# narvi-dac.net
KiCad netlist of a schematic drawn in EAGLE
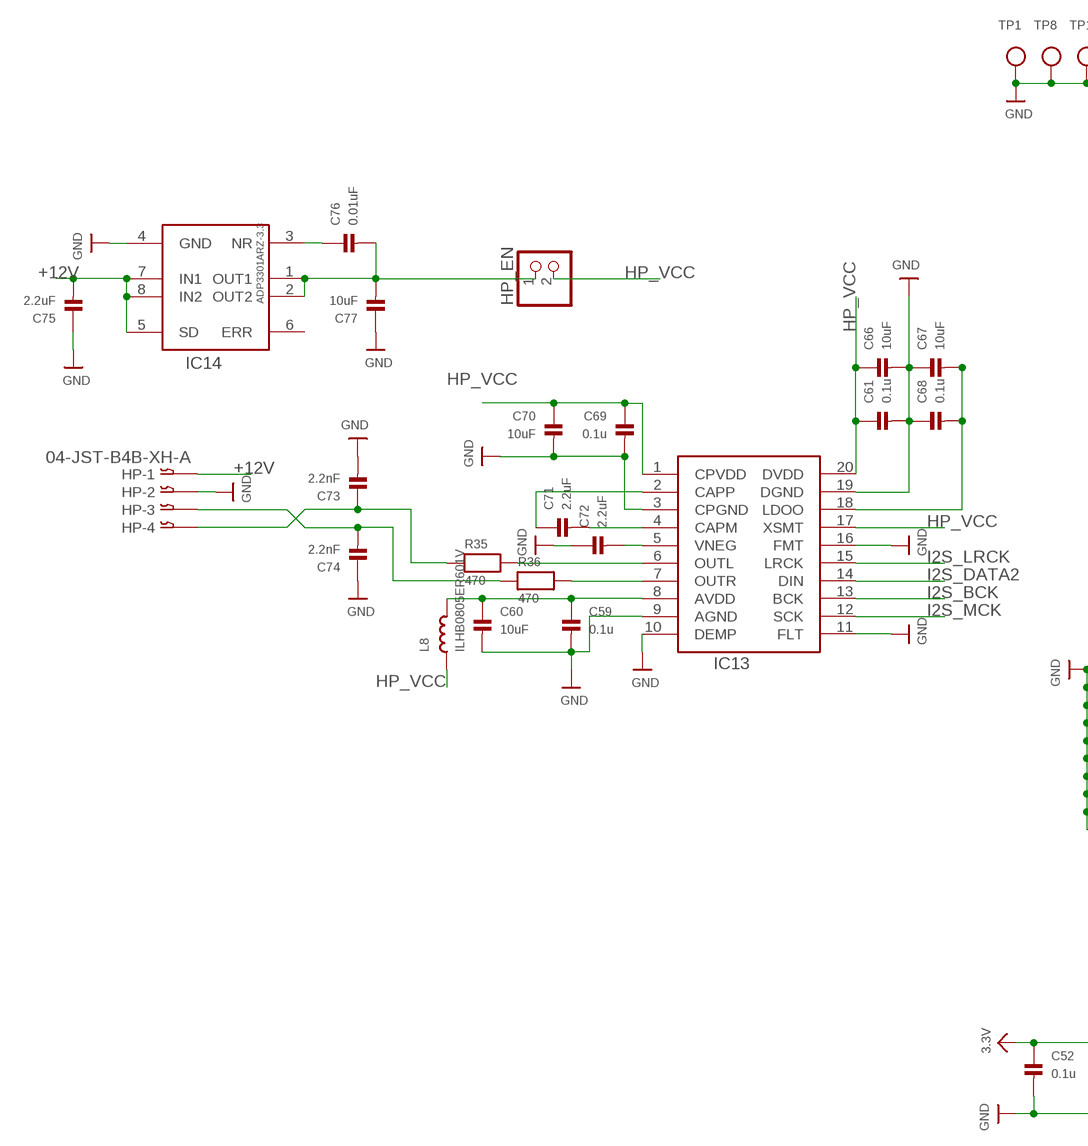
[diagram p0: schematic, sheet 1, part 1 of 2]
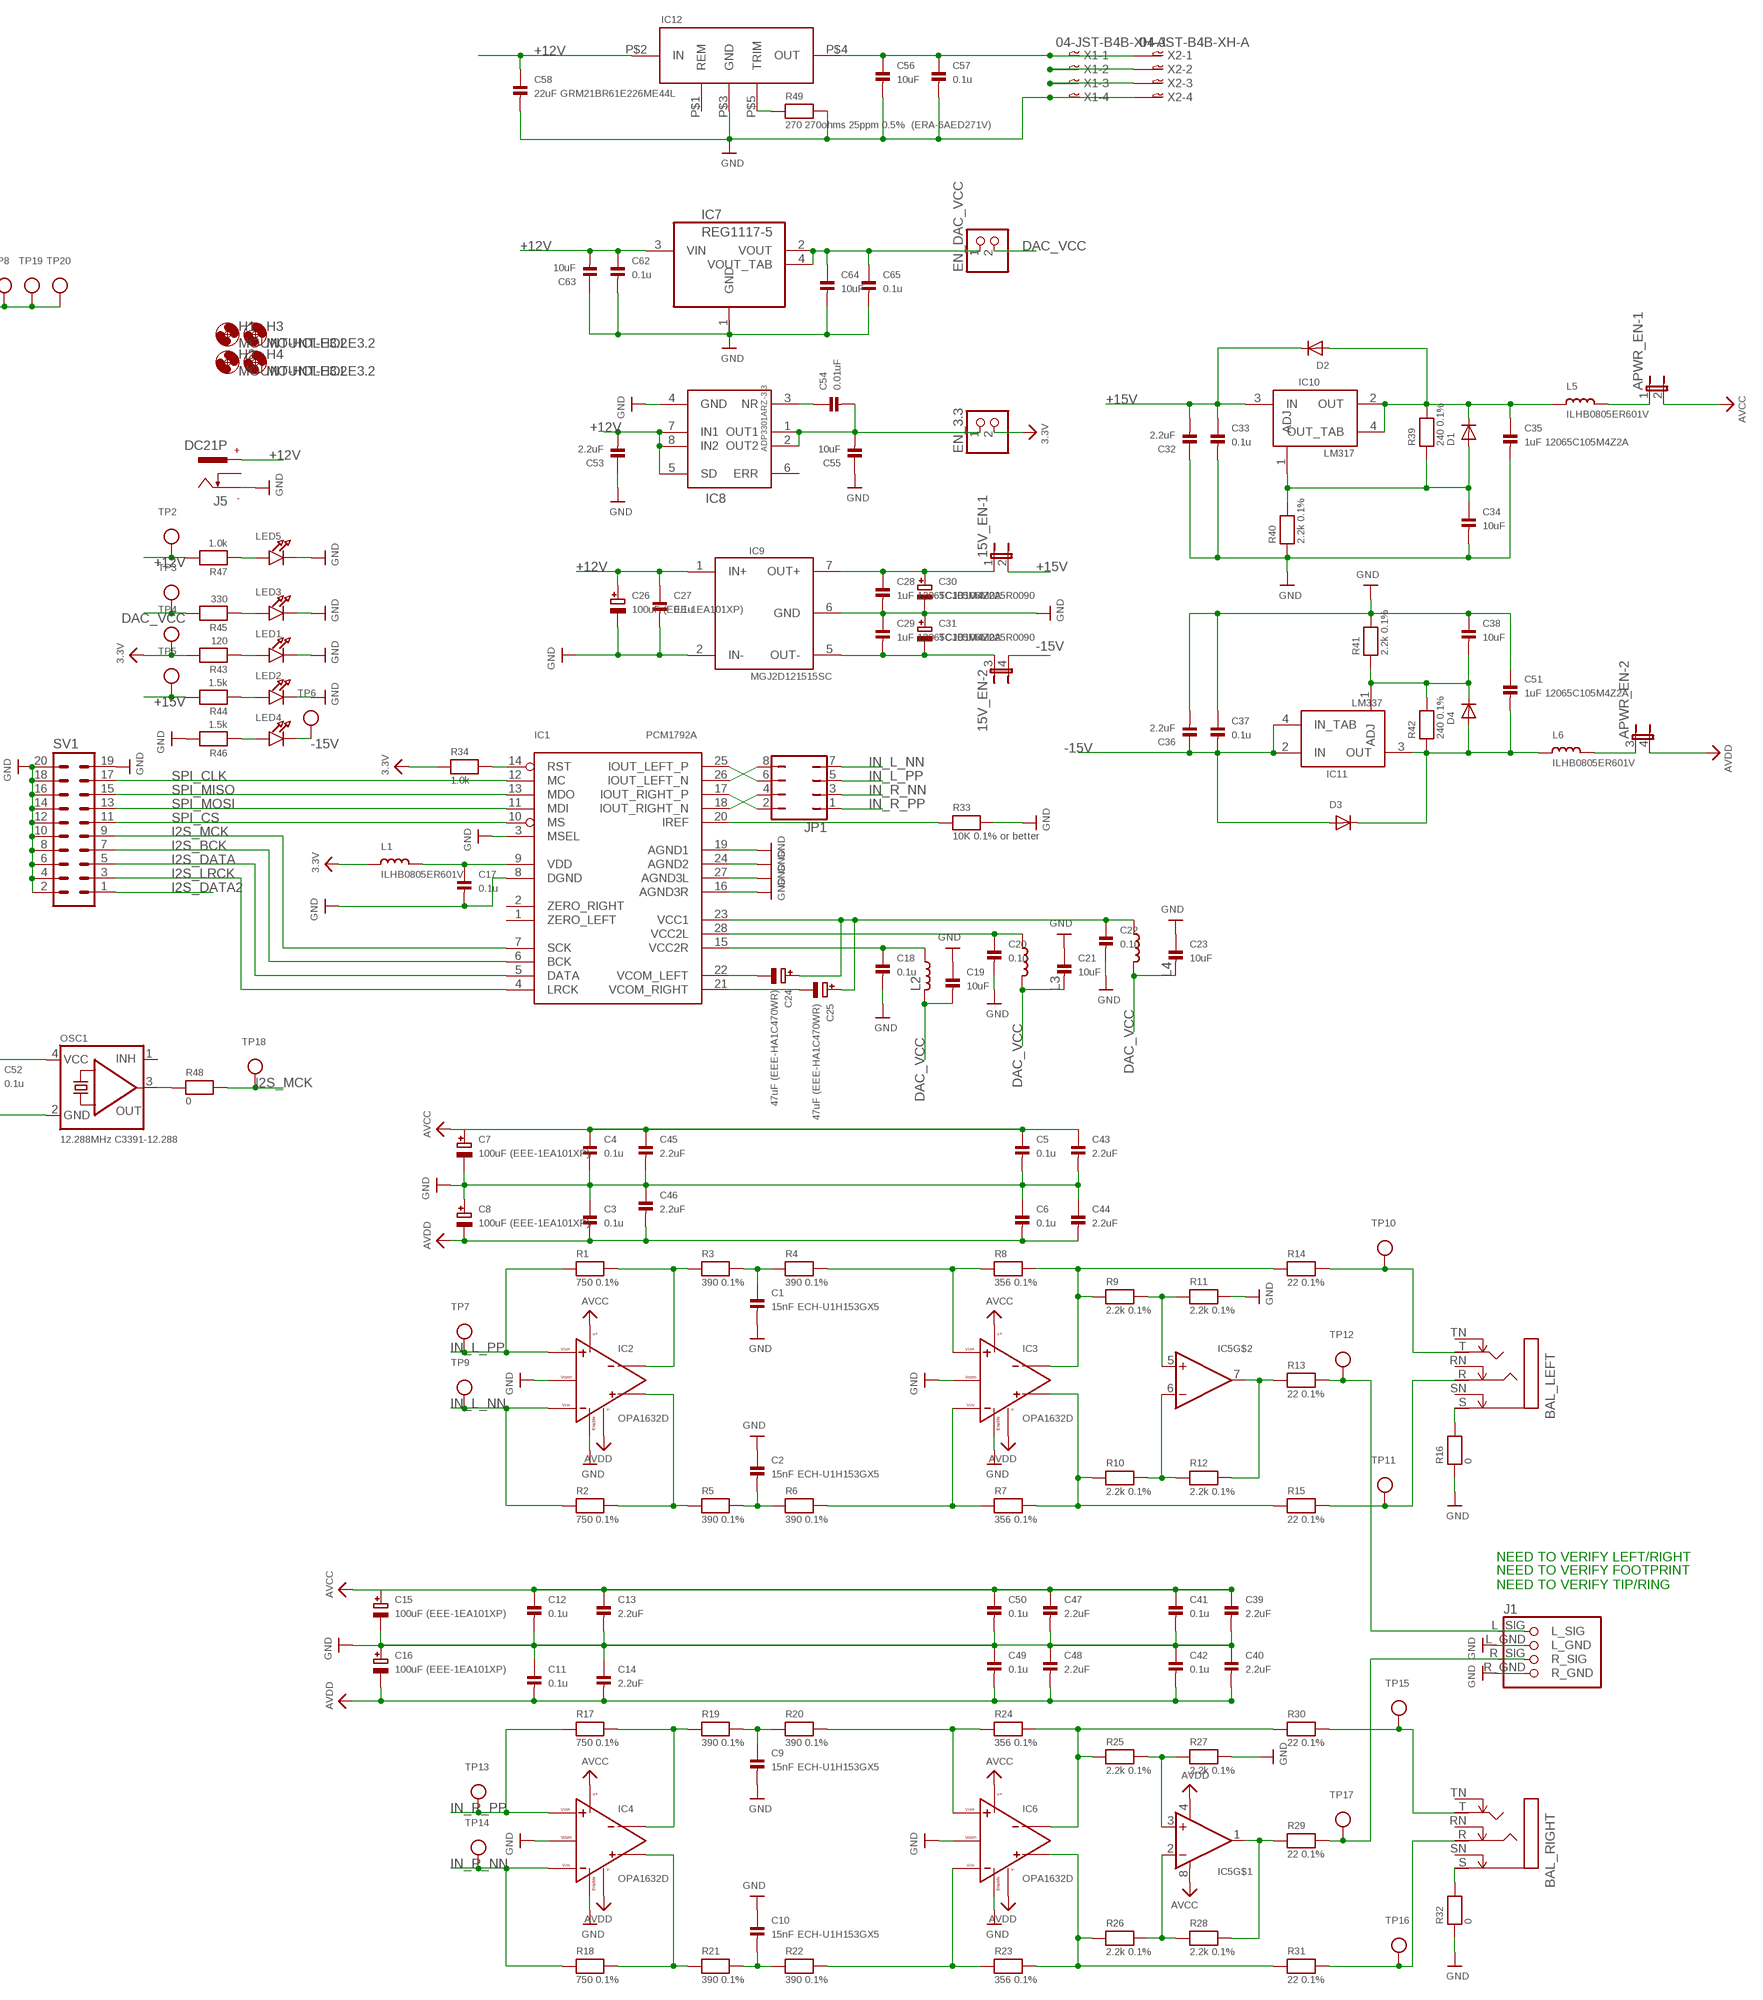
[diagram p1: schematic, sheet 1, part 2 of 2]

(export (version "E")
  (design (tool "Eeschema 10.0.6"))
  (components
    (comp (ref "15V_EN")
      (value "JP2QE")
      (footprint "eagle-import:JP2Q")
      (libsource (lib "eagle-import") (part "JP2QE"))
    )
    (comp (ref "APWR_EN")
      (value "JP2QE")
      (footprint "eagle-import:JP2Q")
      (libsource (lib "eagle-import") (part "JP2QE"))
    )
    (comp (ref "BAL_LEFT")
      (value "STEREOSW")
      (footprint "eagle-import:NMJ6HCD2")
      (libsource (lib "eagle-import") (part "STEREOSW"))
    )
    (comp (ref "BAL_RIGHT")
      (value "STEREOSW")
      (footprint "eagle-import:NMJ6HCD2")
      (libsource (lib "eagle-import") (part "STEREOSW"))
    )
    (comp (ref "C1")
      (value "15nF ECH-U1H153GX5")
      (footprint "eagle-import:1210")
      (libsource (lib "eagle-import") (part "CAP-1210"))
    )
    (comp (ref "C2")
      (value "15nF ECH-U1H153GX5")
      (footprint "eagle-import:1210")
      (libsource (lib "eagle-import") (part "CAP-1210"))
    )
    (comp (ref "C3")
      (value "0.1u")
      (footprint "eagle-import:0603")
      (libsource (lib "eagle-import") (part "CAP_CERAMIC0603"))
    )
    (comp (ref "C4")
      (value "0.1u")
      (footprint "eagle-import:0603")
      (libsource (lib "eagle-import") (part "CAP_CERAMIC0603"))
    )
    (comp (ref "C5")
      (value "0.1u")
      (footprint "eagle-import:0603")
      (libsource (lib "eagle-import") (part "CAP_CERAMIC0603"))
    )
    (comp (ref "C6")
      (value "0.1u")
      (footprint "eagle-import:0603")
      (libsource (lib "eagle-import") (part "CAP_CERAMIC0603"))
    )
    (comp (ref "C7")
      (value "100uF (EEE-1EA101XP)")
      (footprint "eagle-import:PANASONIC_D")
      (libsource (lib "eagle-import") (part "CAP_ELECTROLYTICPANASONIC_D"))
    )
    (comp (ref "C8")
      (value "100uF (EEE-1EA101XP)")
      (footprint "eagle-import:PANASONIC_D")
      (libsource (lib "eagle-import") (part "CAP_ELECTROLYTICPANASONIC_D"))
    )
    (comp (ref "C9")
      (value "15nF ECH-U1H153GX5")
      (footprint "eagle-import:1210")
      (libsource (lib "eagle-import") (part "CAP-1210"))
    )
    (comp (ref "C10")
      (value "15nF ECH-U1H153GX5")
      (footprint "eagle-import:1210")
      (libsource (lib "eagle-import") (part "CAP-1210"))
    )
    (comp (ref "C11")
      (value "0.1u")
      (footprint "eagle-import:0603")
      (libsource (lib "eagle-import") (part "CAP_CERAMIC0603"))
    )
    (comp (ref "C12")
      (value "0.1u")
      (footprint "eagle-import:0603")
      (libsource (lib "eagle-import") (part "CAP_CERAMIC0603"))
    )
    (comp (ref "C13")
      (value "2.2uF")
      (footprint "eagle-import:_0805")
      (libsource (lib "eagle-import") (part "CAP_CERAMIC_0805"))
    )
    (comp (ref "C14")
      (value "2.2uF")
      (footprint "eagle-import:_0805")
      (libsource (lib "eagle-import") (part "CAP_CERAMIC_0805"))
    )
    (comp (ref "C15")
      (value "100uF (EEE-1EA101XP)")
      (footprint "eagle-import:PANASONIC_D")
      (libsource (lib "eagle-import") (part "CAP_ELECTROLYTICPANASONIC_D"))
    )
    (comp (ref "C16")
      (value "100uF (EEE-1EA101XP)")
      (footprint "eagle-import:PANASONIC_D")
      (libsource (lib "eagle-import") (part "CAP_ELECTROLYTICPANASONIC_D"))
    )
    (comp (ref "C17")
      (value "0.1u")
      (footprint "eagle-import:0603")
      (libsource (lib "eagle-import") (part "CAP_CERAMIC0603"))
    )
    (comp (ref "C18")
      (value "0.1u")
      (footprint "eagle-import:0603")
      (libsource (lib "eagle-import") (part "CAP_CERAMIC0603"))
    )
    (comp (ref "C19")
      (value "10uF")
      (footprint "eagle-import:0805")
      (libsource (lib "eagle-import") (part "CAP_CERAMIC0805"))
    )
    (comp (ref "C20")
      (value "0.1u")
      (footprint "eagle-import:0603")
      (libsource (lib "eagle-import") (part "CAP_CERAMIC0603"))
    )
    (comp (ref "C21")
      (value "10uF")
      (footprint "eagle-import:0805")
      (libsource (lib "eagle-import") (part "CAP_CERAMIC0805"))
    )
    (comp (ref "C22")
      (value "0.1u")
      (footprint "eagle-import:0603")
      (libsource (lib "eagle-import") (part "CAP_CERAMIC0603"))
    )
    (comp (ref "C23")
      (value "10uF")
      (footprint "eagle-import:0805")
      (libsource (lib "eagle-import") (part "CAP_CERAMIC0805"))
    )
    (comp (ref "C24")
      (value "47uF (EEE-HA1C470WR)")
      (footprint "eagle-import:PANASONIC_C")
      (libsource (lib "eagle-import") (part "CAP_ELECTROLYTICPANASONIC_C"))
    )
    (comp (ref "C25")
      (value "47uF (EEE-HA1C470WR)")
      (footprint "eagle-import:PANASONIC_C")
      (libsource (lib "eagle-import") (part "CAP_ELECTROLYTICPANASONIC_C"))
    )
    (comp (ref "C26")
      (value "100uF (EEE-1EA101XP)")
      (footprint "eagle-import:PANASONIC_D")
      (libsource (lib "eagle-import") (part "CAP_ELECTROLYTICPANASONIC_D"))
    )
    (comp (ref "C27")
      (value "0.1u")
      (footprint "eagle-import:0603")
      (libsource (lib "eagle-import") (part "CAP_CERAMIC0603"))
    )
    (comp (ref "C28")
      (value "1uF 12065C105M4Z2A")
      (footprint "eagle-import:1206")
      (libsource (lib "eagle-import") (part "CAP_CERAMIC1206"))
    )
    (comp (ref "C29")
      (value "1uF 12065C105M4Z2A")
      (footprint "eagle-import:1206")
      (libsource (lib "eagle-import") (part "CAP_CERAMIC1206"))
    )
    (comp (ref "C30")
      (value "TCJB106M025R0090")
      (footprint "eagle-import:1210POL")
      (libsource (lib "eagle-import") (part "CAP-POL-1210"))
    )
    (comp (ref "C31")
      (value "TCJB106M025R0090")
      (footprint "eagle-import:1210POL")
      (libsource (lib "eagle-import") (part "CAP-POL-1210"))
    )
    (comp (ref "C32")
      (value "2.2uF")
      (footprint "eagle-import:_0805")
      (libsource (lib "eagle-import") (part "CAP_CERAMIC_0805"))
    )
    (comp (ref "C33")
      (value "0.1u")
      (footprint "eagle-import:0603")
      (libsource (lib "eagle-import") (part "CAP_CERAMIC0603"))
    )
    (comp (ref "C34")
      (value "10uF")
      (footprint "eagle-import:0805")
      (libsource (lib "eagle-import") (part "CAP_CERAMIC0805"))
    )
    (comp (ref "C35")
      (value "1uF 12065C105M4Z2A")
      (footprint "eagle-import:1206")
      (libsource (lib "eagle-import") (part "CAP_CERAMIC1206"))
    )
    (comp (ref "C36")
      (value "2.2uF")
      (footprint "eagle-import:_0805")
      (libsource (lib "eagle-import") (part "CAP_CERAMIC_0805"))
    )
    (comp (ref "C37")
      (value "0.1u")
      (footprint "eagle-import:0603")
      (libsource (lib "eagle-import") (part "CAP_CERAMIC0603"))
    )
    (comp (ref "C38")
      (value "10uF")
      (footprint "eagle-import:0805")
      (libsource (lib "eagle-import") (part "CAP_CERAMIC0805"))
    )
    (comp (ref "C39")
      (value "2.2uF")
      (footprint "eagle-import:_0805")
      (libsource (lib "eagle-import") (part "CAP_CERAMIC_0805"))
    )
    (comp (ref "C40")
      (value "2.2uF")
      (footprint "eagle-import:_0805")
      (libsource (lib "eagle-import") (part "CAP_CERAMIC_0805"))
    )
    (comp (ref "C41")
      (value "0.1u")
      (footprint "eagle-import:0603")
      (libsource (lib "eagle-import") (part "CAP_CERAMIC0603"))
    )
    (comp (ref "C42")
      (value "0.1u")
      (footprint "eagle-import:0603")
      (libsource (lib "eagle-import") (part "CAP_CERAMIC0603"))
    )
    (comp (ref "C43")
      (value "2.2uF")
      (footprint "eagle-import:_0805")
      (libsource (lib "eagle-import") (part "CAP_CERAMIC_0805"))
    )
    (comp (ref "C44")
      (value "2.2uF")
      (footprint "eagle-import:_0805")
      (libsource (lib "eagle-import") (part "CAP_CERAMIC_0805"))
    )
    (comp (ref "C45")
      (value "2.2uF")
      (footprint "eagle-import:_0805")
      (libsource (lib "eagle-import") (part "CAP_CERAMIC_0805"))
    )
    (comp (ref "C46")
      (value "2.2uF")
      (footprint "eagle-import:_0805")
      (libsource (lib "eagle-import") (part "CAP_CERAMIC_0805"))
    )
    (comp (ref "C47")
      (value "2.2uF")
      (footprint "eagle-import:_0805")
      (libsource (lib "eagle-import") (part "CAP_CERAMIC_0805"))
    )
    (comp (ref "C48")
      (value "2.2uF")
      (footprint "eagle-import:_0805")
      (libsource (lib "eagle-import") (part "CAP_CERAMIC_0805"))
    )
    (comp (ref "C49")
      (value "0.1u")
      (footprint "eagle-import:0603")
      (libsource (lib "eagle-import") (part "CAP_CERAMIC0603"))
    )
    (comp (ref "C50")
      (value "0.1u")
      (footprint "eagle-import:0603")
      (libsource (lib "eagle-import") (part "CAP_CERAMIC0603"))
    )
    (comp (ref "C51")
      (value "1uF 12065C105M4Z2A")
      (footprint "eagle-import:1206")
      (libsource (lib "eagle-import") (part "CAP_CERAMIC1206"))
    )
    (comp (ref "C52")
      (value "0.1u")
      (footprint "eagle-import:0603")
      (libsource (lib "eagle-import") (part "CAP_CERAMIC0603"))
    )
    (comp (ref "C53")
      (value "2.2uF")
      (footprint "eagle-import:_0805")
      (libsource (lib "eagle-import") (part "CAP_CERAMIC_0805"))
    )
    (comp (ref "C54")
      (value "0.01uF")
      (footprint "eagle-import:0603")
      (libsource (lib "eagle-import") (part "CAP_CERAMIC0603"))
    )
    (comp (ref "C55")
      (value "10uF")
      (footprint "eagle-import:0805")
      (libsource (lib "eagle-import") (part "CAP_CERAMIC0805"))
    )
    (comp (ref "C56")
      (value "10uF")
      (footprint "eagle-import:0805")
      (libsource (lib "eagle-import") (part "CAP_CERAMIC0805"))
    )
    (comp (ref "C57")
      (value "0.1u")
      (footprint "eagle-import:0603")
      (libsource (lib "eagle-import") (part "CAP_CERAMIC0603"))
    )
    (comp (ref "C58")
      (value "22uF GRM21BR61E226ME44L")
      (footprint "eagle-import:_0805")
      (libsource (lib "eagle-import") (part "CAP_CERAMIC_0805"))
    )
    (comp (ref "C59")
      (value "0.1u")
      (footprint "eagle-import:0603")
      (libsource (lib "eagle-import") (part "CAP_CERAMIC0603"))
    )
    (comp (ref "C60")
      (value "10uF")
      (footprint "eagle-import:0805")
      (libsource (lib "eagle-import") (part "CAP_CERAMIC0805"))
    )
    (comp (ref "C61")
      (value "0.1u")
      (footprint "eagle-import:0603")
      (libsource (lib "eagle-import") (part "CAP_CERAMIC0603"))
    )
    (comp (ref "C62")
      (value "0.1u")
      (footprint "eagle-import:0603")
      (libsource (lib "eagle-import") (part "CAP_CERAMIC0603"))
    )
    (comp (ref "C63")
      (value "10uF")
      (footprint "eagle-import:0805")
      (libsource (lib "eagle-import") (part "CAP_CERAMIC0805"))
    )
    (comp (ref "C64")
      (value "10uF")
      (footprint "eagle-import:0805")
      (libsource (lib "eagle-import") (part "CAP_CERAMIC0805"))
    )
    (comp (ref "C65")
      (value "0.1u")
      (footprint "eagle-import:0603")
      (libsource (lib "eagle-import") (part "CAP_CERAMIC0603"))
    )
    (comp (ref "C66")
      (value "10uF")
      (footprint "eagle-import:0805")
      (libsource (lib "eagle-import") (part "CAP_CERAMIC0805"))
    )
    (comp (ref "C67")
      (value "10uF")
      (footprint "eagle-import:0805")
      (libsource (lib "eagle-import") (part "CAP_CERAMIC0805"))
    )
    (comp (ref "C68")
      (value "0.1u")
      (footprint "eagle-import:0603")
      (libsource (lib "eagle-import") (part "CAP_CERAMIC0603"))
    )
    (comp (ref "C69")
      (value "0.1u")
      (footprint "eagle-import:0603")
      (libsource (lib "eagle-import") (part "CAP_CERAMIC0603"))
    )
    (comp (ref "C70")
      (value "10uF")
      (footprint "eagle-import:0805")
      (libsource (lib "eagle-import") (part "CAP_CERAMIC0805"))
    )
    (comp (ref "C71")
      (value "2.2uF")
      (footprint "eagle-import:_0805")
      (libsource (lib "eagle-import") (part "CAP_CERAMIC_0805"))
    )
    (comp (ref "C72")
      (value "2.2uF")
      (footprint "eagle-import:_0805")
      (libsource (lib "eagle-import") (part "CAP_CERAMIC_0805"))
    )
    (comp (ref "C73")
      (value "2.2nF")
      (footprint "eagle-import:_0805")
      (libsource (lib "eagle-import") (part "CAP_CERAMIC_0805"))
    )
    (comp (ref "C74")
      (value "2.2nF")
      (footprint "eagle-import:_0805")
      (libsource (lib "eagle-import") (part "CAP_CERAMIC_0805"))
    )
    (comp (ref "C75")
      (value "2.2uF")
      (footprint "eagle-import:_0805")
      (libsource (lib "eagle-import") (part "CAP_CERAMIC_0805"))
    )
    (comp (ref "C76")
      (value "0.01uF")
      (footprint "eagle-import:0603")
      (libsource (lib "eagle-import") (part "CAP_CERAMIC0603"))
    )
    (comp (ref "C77")
      (value "10uF")
      (footprint "eagle-import:0805")
      (libsource (lib "eagle-import") (part "CAP_CERAMIC0805"))
    )
    (comp (ref "D1")
      (value "DIODESOD-123")
      (footprint "eagle-import:SOD-123")
      (libsource (lib "eagle-import") (part "DIODESOD-123"))
    )
    (comp (ref "D2")
      (value "DIODESOD-123")
      (footprint "eagle-import:SOD-123")
      (libsource (lib "eagle-import") (part "DIODESOD-123"))
    )
    (comp (ref "D3")
      (value "DIODESOD-123")
      (footprint "eagle-import:SOD-123")
      (libsource (lib "eagle-import") (part "DIODESOD-123"))
    )
    (comp (ref "D4")
      (value "DIODESOD-123")
      (footprint "eagle-import:SOD-123")
      (libsource (lib "eagle-import") (part "DIODESOD-123"))
    )
    (comp (ref "EN_3.3")
      (value "HEADER-1X2")
      (footprint "eagle-import:1X02_OVAL")
      (libsource (lib "eagle-import") (part "HEADER-1X2"))
    )
    (comp (ref "EN_DAC_VCC")
      (value "HEADER-1X2")
      (footprint "eagle-import:1X02_OVAL")
      (libsource (lib "eagle-import") (part "HEADER-1X2"))
    )
    (comp (ref "H1")
      (value "MOUNT-HOLE3.2")
      (footprint "eagle-import:3,2")
      (libsource (lib "eagle-import") (part "MOUNT-HOLE3.2"))
    )
    (comp (ref "H2")
      (value "MOUNT-HOLE3.2")
      (footprint "eagle-import:3,2")
      (libsource (lib "eagle-import") (part "MOUNT-HOLE3.2"))
    )
    (comp (ref "H3")
      (value "MOUNT-HOLE3.2")
      (footprint "eagle-import:3,2")
      (libsource (lib "eagle-import") (part "MOUNT-HOLE3.2"))
    )
    (comp (ref "H4")
      (value "MOUNT-HOLE3.2")
      (footprint "eagle-import:3,2")
      (libsource (lib "eagle-import") (part "MOUNT-HOLE3.2"))
    )
    (comp (ref "HP")
      (value "04-JST-B4B-XH-A")
      (footprint "eagle-import:B4B-XH")
      (fields (field (name "MPN") "B4B-XH-A(LF)(SN)"))
      (libsource (lib "eagle-import") (part "04-JST-B4B-XH-A"))
    )
    (comp (ref "HP_EN")
      (value "HEADER-1X2")
      (footprint "eagle-import:1X02_OVAL")
      (libsource (lib "eagle-import") (part "HEADER-1X2"))
    )
    (comp (ref "IC1")
      (value "PCM1792A")
      (footprint "eagle-import:SSOP28")
      (libsource (lib "eagle-import") (part "PCM1792A"))
    )
    (comp (ref "IC2")
      (value "OPA1632D")
      (footprint "eagle-import:SO08")
      (libsource (lib "eagle-import") (part "OPA1632D"))
    )
    (comp (ref "IC3")
      (value "OPA1632D")
      (footprint "eagle-import:SO08")
      (libsource (lib "eagle-import") (part "OPA1632D"))
    )
    (comp (ref "IC4")
      (value "OPA1632D")
      (footprint "eagle-import:SO08")
      (libsource (lib "eagle-import") (part "OPA1632D"))
    )
    (comp (ref "IC5")
      (value "LM4562")
      (footprint "eagle-import:SOIC8_150MIL")
      (libsource (lib "eagle-import") (part "LM4562"))
    )
    (comp (ref "IC6")
      (value "OPA1632D")
      (footprint "eagle-import:SO08")
      (libsource (lib "eagle-import") (part "OPA1632D"))
    )
    (comp (ref "IC7")
      (value "REG1117-5")
      (footprint "eagle-import:SOT223")
      (fields (field (name "MPN") "REG1117"))
      (libsource (lib "eagle-import") (part "REG1117"))
    )
    (comp (ref "IC8")
      (value "ADP3301ARZ-3.3")
      (footprint "eagle-import:SO08")
      (libsource (lib "eagle-import") (part "ADP3301"))
    )
    (comp (ref "IC9")
      (value "MGJ2D121515SC")
      (footprint "eagle-import:MURATA-MGJ2")
      (libsource (lib "eagle-import") (part "MURATA-MGJ2"))
    )
    (comp (ref "IC10")
      (value "LM317")
      (footprint "eagle-import:SOT223")
      (libsource (lib "eagle-import") (part "LM317"))
    )
    (comp (ref "IC11")
      (value "LM337")
      (footprint "eagle-import:SOT223")
      (libsource (lib "eagle-import") (part "LM337"))
    )
    (comp (ref "IC12")
      (value "MURATA_OKR-T/10-W12-C")
      (footprint "eagle-import:MURATA_OKR-T_10-W12-C")
      (libsource (lib "eagle-import") (part "MURATA_OKR-T/10-W12-C"))
    )
    (comp (ref "IC13")
      (value "PCM5102")
      (footprint "eagle-import:TSSOP20")
      (libsource (lib "eagle-import") (part "PCM5102"))
    )
    (comp (ref "IC14")
      (value "ADP3301ARZ-3.3")
      (footprint "eagle-import:SO08")
      (libsource (lib "eagle-import") (part "ADP3301"))
    )
    (comp (ref "J1")
      (value "CUI-RCJ-2123")
      (footprint "eagle-import:CUI-RCJ-2123")
      (libsource (lib "eagle-import") (part "CUI-RCJ-2123"))
    )
    (comp (ref "J5")
      (value "DC21P")
      (footprint "eagle-import:CUI-PJ-102AH")
      (libsource (lib "eagle-import") (part "DC21P"))
    )
    (comp (ref "JP1")
      (value "JP4Q")
      (footprint "eagle-import:JP4Q")
      (libsource (lib "eagle-import") (part "JP4Q"))
    )
    (comp (ref "L1")
      (value "ILHB0805ER601V")
      (footprint "eagle-import:_0805")
      (libsource (lib "eagle-import") (part "INDUCTOR_0805"))
    )
    (comp (ref "L2")
      (value "ILHB0805ER601V")
      (footprint "eagle-import:_0805")
      (libsource (lib "eagle-import") (part "INDUCTOR_0805"))
    )
    (comp (ref "L3")
      (value "ILHB0805ER601V")
      (footprint "eagle-import:_0805")
      (libsource (lib "eagle-import") (part "INDUCTOR_0805"))
    )
    (comp (ref "L4")
      (value "ILHB0805ER601V")
      (footprint "eagle-import:_0805")
      (libsource (lib "eagle-import") (part "INDUCTOR_0805"))
    )
    (comp (ref "L5")
      (value "ILHB0805ER601V")
      (footprint "eagle-import:_0805")
      (libsource (lib "eagle-import") (part "INDUCTOR_0805"))
    )
    (comp (ref "L6")
      (value "ILHB0805ER601V")
      (footprint "eagle-import:_0805")
      (libsource (lib "eagle-import") (part "INDUCTOR_0805"))
    )
    (comp (ref "L8")
      (value "ILHB0805ER601V")
      (footprint "eagle-import:_0805")
      (libsource (lib "eagle-import") (part "INDUCTOR_0805"))
    )
    (comp (ref "LED1")
      (value "LED0805")
      (footprint "eagle-import:CHIPLED_0805")
      (libsource (lib "eagle-import") (part "LED0805"))
    )
    (comp (ref "LED2")
      (value "LED0805")
      (footprint "eagle-import:CHIPLED_0805")
      (libsource (lib "eagle-import") (part "LED0805"))
    )
    (comp (ref "LED3")
      (value "LED0805")
      (footprint "eagle-import:CHIPLED_0805")
      (libsource (lib "eagle-import") (part "LED0805"))
    )
    (comp (ref "LED4")
      (value "LED0805")
      (footprint "eagle-import:CHIPLED_0805")
      (libsource (lib "eagle-import") (part "LED0805"))
    )
    (comp (ref "LED5")
      (value "LED0805")
      (footprint "eagle-import:CHIPLED_0805")
      (libsource (lib "eagle-import") (part "LED0805"))
    )
    (comp (ref "OSC1")
      (value "12.288MHz C3391-12.288")
      (footprint "eagle-import:OSC_7X5MM")
      (libsource (lib "eagle-import") (part "OSCILLATOR"))
    )
    (comp (ref "R1")
      (value "750 0.1%")
      (footprint "eagle-import:_0805")
      (libsource (lib "eagle-import") (part "RESISTOR_0805"))
    )
    (comp (ref "R2")
      (value "750 0.1%")
      (footprint "eagle-import:_0805")
      (libsource (lib "eagle-import") (part "RESISTOR_0805"))
    )
    (comp (ref "R3")
      (value "390 0.1%")
      (footprint "eagle-import:_0805")
      (libsource (lib "eagle-import") (part "RESISTOR_0805"))
    )
    (comp (ref "R4")
      (value "390 0.1%")
      (footprint "eagle-import:_0805")
      (libsource (lib "eagle-import") (part "RESISTOR_0805"))
    )
    (comp (ref "R5")
      (value "390 0.1%")
      (footprint "eagle-import:_0805")
      (libsource (lib "eagle-import") (part "RESISTOR_0805"))
    )
    (comp (ref "R6")
      (value "390 0.1%")
      (footprint "eagle-import:_0805")
      (libsource (lib "eagle-import") (part "RESISTOR_0805"))
    )
    (comp (ref "R7")
      (value "356 0.1%")
      (footprint "eagle-import:_0805")
      (libsource (lib "eagle-import") (part "RESISTOR_0805"))
    )
    (comp (ref "R8")
      (value "356 0.1%")
      (footprint "eagle-import:_0805")
      (libsource (lib "eagle-import") (part "RESISTOR_0805"))
    )
    (comp (ref "R9")
      (value "2.2k 0.1%")
      (footprint "eagle-import:_0805")
      (libsource (lib "eagle-import") (part "RESISTOR_0805"))
    )
    (comp (ref "R10")
      (value "2.2k 0.1%")
      (footprint "eagle-import:_0805")
      (libsource (lib "eagle-import") (part "RESISTOR_0805"))
    )
    (comp (ref "R11")
      (value "2.2k 0.1%")
      (footprint "eagle-import:_0805")
      (libsource (lib "eagle-import") (part "RESISTOR_0805"))
    )
    (comp (ref "R12")
      (value "2.2k 0.1%")
      (footprint "eagle-import:_0805")
      (libsource (lib "eagle-import") (part "RESISTOR_0805"))
    )
    (comp (ref "R13")
      (value "22 0.1%")
      (footprint "eagle-import:_0805")
      (libsource (lib "eagle-import") (part "RESISTOR_0805"))
    )
    (comp (ref "R14")
      (value "22 0.1%")
      (footprint "eagle-import:_0805")
      (libsource (lib "eagle-import") (part "RESISTOR_0805"))
    )
    (comp (ref "R15")
      (value "22 0.1%")
      (footprint "eagle-import:_0805")
      (libsource (lib "eagle-import") (part "RESISTOR_0805"))
    )
    (comp (ref "R16")
      (value "0")
      (footprint "eagle-import:_0805")
      (libsource (lib "eagle-import") (part "RESISTOR_0805"))
    )
    (comp (ref "R17")
      (value "750 0.1%")
      (footprint "eagle-import:_0805")
      (libsource (lib "eagle-import") (part "RESISTOR_0805"))
    )
    (comp (ref "R18")
      (value "750 0.1%")
      (footprint "eagle-import:_0805")
      (libsource (lib "eagle-import") (part "RESISTOR_0805"))
    )
    (comp (ref "R19")
      (value "390 0.1%")
      (footprint "eagle-import:_0805")
      (libsource (lib "eagle-import") (part "RESISTOR_0805"))
    )
    (comp (ref "R20")
      (value "390 0.1%")
      (footprint "eagle-import:_0805")
      (libsource (lib "eagle-import") (part "RESISTOR_0805"))
    )
    (comp (ref "R21")
      (value "390 0.1%")
      (footprint "eagle-import:_0805")
      (libsource (lib "eagle-import") (part "RESISTOR_0805"))
    )
    (comp (ref "R22")
      (value "390 0.1%")
      (footprint "eagle-import:_0805")
      (libsource (lib "eagle-import") (part "RESISTOR_0805"))
    )
    (comp (ref "R23")
      (value "356 0.1%")
      (footprint "eagle-import:_0805")
      (libsource (lib "eagle-import") (part "RESISTOR_0805"))
    )
    (comp (ref "R24")
      (value "356 0.1%")
      (footprint "eagle-import:_0805")
      (libsource (lib "eagle-import") (part "RESISTOR_0805"))
    )
    (comp (ref "R25")
      (value "2.2k 0.1%")
      (footprint "eagle-import:_0805")
      (libsource (lib "eagle-import") (part "RESISTOR_0805"))
    )
    (comp (ref "R26")
      (value "2.2k 0.1%")
      (footprint "eagle-import:_0805")
      (libsource (lib "eagle-import") (part "RESISTOR_0805"))
    )
    (comp (ref "R27")
      (value "2.2k 0.1%")
      (footprint "eagle-import:_0805")
      (libsource (lib "eagle-import") (part "RESISTOR_0805"))
    )
    (comp (ref "R28")
      (value "2.2k 0.1%")
      (footprint "eagle-import:_0805")
      (libsource (lib "eagle-import") (part "RESISTOR_0805"))
    )
    (comp (ref "R29")
      (value "22 0.1%")
      (footprint "eagle-import:_0805")
      (libsource (lib "eagle-import") (part "RESISTOR_0805"))
    )
    (comp (ref "R30")
      (value "22 0.1%")
      (footprint "eagle-import:_0805")
      (libsource (lib "eagle-import") (part "RESISTOR_0805"))
    )
    (comp (ref "R31")
      (value "22 0.1%")
      (footprint "eagle-import:_0805")
      (libsource (lib "eagle-import") (part "RESISTOR_0805"))
    )
    (comp (ref "R32")
      (value "0")
      (footprint "eagle-import:_0805")
      (libsource (lib "eagle-import") (part "RESISTOR_0805"))
    )
    (comp (ref "R33")
      (value "10K 0.1% or better")
      (footprint "eagle-import:_0805")
      (libsource (lib "eagle-import") (part "RESISTOR_0805"))
    )
    (comp (ref "R34")
      (value "1.0k")
      (footprint "eagle-import:_0805")
      (libsource (lib "eagle-import") (part "RESISTOR_0805"))
    )
    (comp (ref "R35")
      (value "470")
      (footprint "eagle-import:_0805")
      (libsource (lib "eagle-import") (part "RESISTOR_0805"))
    )
    (comp (ref "R36")
      (value "470")
      (footprint "eagle-import:_0805")
      (libsource (lib "eagle-import") (part "RESISTOR_0805"))
    )
    (comp (ref "R39")
      (value "240 0.1%")
      (footprint "eagle-import:_0805")
      (libsource (lib "eagle-import") (part "RESISTOR_0805"))
    )
    (comp (ref "R40")
      (value "2.2k 0.1%")
      (footprint "eagle-import:_0805")
      (libsource (lib "eagle-import") (part "RESISTOR_0805"))
    )
    (comp (ref "R41")
      (value "2.2k 0.1%")
      (footprint "eagle-import:_0805")
      (libsource (lib "eagle-import") (part "RESISTOR_0805"))
    )
    (comp (ref "R42")
      (value "240 0.1%")
      (footprint "eagle-import:_0805")
      (libsource (lib "eagle-import") (part "RESISTOR_0805"))
    )
    (comp (ref "R43")
      (value "120")
      (footprint "eagle-import:_0805")
      (libsource (lib "eagle-import") (part "RESISTOR_0805"))
    )
    (comp (ref "R44")
      (value "1.5k")
      (footprint "eagle-import:_0805")
      (libsource (lib "eagle-import") (part "RESISTOR_0805"))
    )
    (comp (ref "R45")
      (value "330")
      (footprint "eagle-import:_0805")
      (libsource (lib "eagle-import") (part "RESISTOR_0805"))
    )
    (comp (ref "R46")
      (value "1.5k")
      (footprint "eagle-import:_0805")
      (libsource (lib "eagle-import") (part "RESISTOR_0805"))
    )
    (comp (ref "R47")
      (value "1.0k")
      (footprint "eagle-import:_0805")
      (libsource (lib "eagle-import") (part "RESISTOR_0805"))
    )
    (comp (ref "R48")
      (value "0")
      (footprint "eagle-import:_0805")
      (libsource (lib "eagle-import") (part "RESISTOR_0805"))
    )
    (comp (ref "R49")
      (value "270 270ohms 25ppm 0.5% (ERA-6AED271V)")
      (footprint "eagle-import:_0805")
      (libsource (lib "eagle-import") (part "RESISTOR_0805"))
    )
    (comp (ref "SV1")
      (value "ML20")
      (footprint "eagle-import:ML20")
      (libsource (lib "eagle-import") (part "ML20"))
    )
    (comp (ref "TP1")
      (value "TESTPOINT0.1\"")
      (footprint "eagle-import:1X01_ROUND")
      (libsource (lib "eagle-import") (part "TESTPOINT0.1{dblquote}"))
    )
    (comp (ref "TP2")
      (value "TESTPOINT0.1\"")
      (footprint "eagle-import:1X01_ROUND")
      (libsource (lib "eagle-import") (part "TESTPOINT0.1{dblquote}"))
    )
    (comp (ref "TP3")
      (value "TESTPOINT0.1\"")
      (footprint "eagle-import:1X01_ROUND")
      (libsource (lib "eagle-import") (part "TESTPOINT0.1{dblquote}"))
    )
    (comp (ref "TP4")
      (value "TESTPOINT0.1\"")
      (footprint "eagle-import:1X01_ROUND")
      (libsource (lib "eagle-import") (part "TESTPOINT0.1{dblquote}"))
    )
    (comp (ref "TP5")
      (value "TESTPOINT0.1\"")
      (footprint "eagle-import:1X01_ROUND")
      (libsource (lib "eagle-import") (part "TESTPOINT0.1{dblquote}"))
    )
    (comp (ref "TP6")
      (value "TESTPOINT0.1\"")
      (footprint "eagle-import:1X01_ROUND")
      (libsource (lib "eagle-import") (part "TESTPOINT0.1{dblquote}"))
    )
    (comp (ref "TP7")
      (value "TESTPOINT0.1\"")
      (footprint "eagle-import:1X01_ROUND")
      (libsource (lib "eagle-import") (part "TESTPOINT0.1{dblquote}"))
    )
    (comp (ref "TP8")
      (value "TESTPOINT0.1\"")
      (footprint "eagle-import:1X01_ROUND")
      (libsource (lib "eagle-import") (part "TESTPOINT0.1{dblquote}"))
    )
    (comp (ref "TP9")
      (value "TESTPOINT0.1\"")
      (footprint "eagle-import:1X01_ROUND")
      (libsource (lib "eagle-import") (part "TESTPOINT0.1{dblquote}"))
    )
    (comp (ref "TP10")
      (value "TESTPOINT0.1\"")
      (footprint "eagle-import:1X01_ROUND")
      (libsource (lib "eagle-import") (part "TESTPOINT0.1{dblquote}"))
    )
    (comp (ref "TP11")
      (value "TESTPOINT0.1\"")
      (footprint "eagle-import:1X01_ROUND")
      (libsource (lib "eagle-import") (part "TESTPOINT0.1{dblquote}"))
    )
    (comp (ref "TP12")
      (value "TESTPOINT0.1\"")
      (footprint "eagle-import:1X01_ROUND")
      (libsource (lib "eagle-import") (part "TESTPOINT0.1{dblquote}"))
    )
    (comp (ref "TP13")
      (value "TESTPOINT0.1\"")
      (footprint "eagle-import:1X01_ROUND")
      (libsource (lib "eagle-import") (part "TESTPOINT0.1{dblquote}"))
    )
    (comp (ref "TP14")
      (value "TESTPOINT0.1\"")
      (footprint "eagle-import:1X01_ROUND")
      (libsource (lib "eagle-import") (part "TESTPOINT0.1{dblquote}"))
    )
    (comp (ref "TP15")
      (value "TESTPOINT0.1\"")
      (footprint "eagle-import:1X01_ROUND")
      (libsource (lib "eagle-import") (part "TESTPOINT0.1{dblquote}"))
    )
    (comp (ref "TP16")
      (value "TESTPOINT0.1\"")
      (footprint "eagle-import:1X01_ROUND")
      (libsource (lib "eagle-import") (part "TESTPOINT0.1{dblquote}"))
    )
    (comp (ref "TP17")
      (value "TESTPOINT0.1\"")
      (footprint "eagle-import:1X01_ROUND")
      (libsource (lib "eagle-import") (part "TESTPOINT0.1{dblquote}"))
    )
    (comp (ref "TP18")
      (value "TESTPOINT0.1\"")
      (footprint "eagle-import:1X01_ROUND")
      (libsource (lib "eagle-import") (part "TESTPOINT0.1{dblquote}"))
    )
    (comp (ref "TP19")
      (value "TESTPOINT0.1\"")
      (footprint "eagle-import:1X01_ROUND")
      (libsource (lib "eagle-import") (part "TESTPOINT0.1{dblquote}"))
    )
    (comp (ref "TP20")
      (value "TESTPOINT0.1\"")
      (footprint "eagle-import:1X01_ROUND")
      (libsource (lib "eagle-import") (part "TESTPOINT0.1{dblquote}"))
    )
    (comp (ref "X1")
      (value "04-JST-B4B-XH-A")
      (footprint "eagle-import:B4B-XH")
      (fields (field (name "MPN") "B4B-XH-A(LF)(SN)"))
      (libsource (lib "eagle-import") (part "04-JST-B4B-XH-A"))
    )
    (comp (ref "X2")
      (value "04-JST-B4B-XH-A")
      (footprint "eagle-import:B4B-XH")
      (fields (field (name "MPN") "B4B-XH-A(LF)(SN)"))
      (libsource (lib "eagle-import") (part "04-JST-B4B-XH-A"))
    )
  )
  (nets
    (net (code "1") (name "/+12V") (class "Default")
      (node (ref "C26") (pin "+") (pinfunction "+_+") (pintype "passive"))
      (node (ref "C27") (pin "1") (pinfunction "P$1_1") (pintype "passive"))
      (node (ref "C53") (pin "2") (pinfunction "P$2_2") (pintype "passive"))
      (node (ref "C58") (pin "1") (pinfunction "P$1_1") (pintype "passive"))
      (node (ref "C62") (pin "1") (pinfunction "P$1_1") (pintype "passive"))
      (node (ref "C63") (pin "2") (pinfunction "P$2_2") (pintype "passive"))
      (node (ref "C75") (pin "2") (pinfunction "P$2_2") (pintype "passive"))
      (node (ref "HP") (pin "P$1") (pinfunction "1_P$1") (pintype "passive"))
      (node (ref "IC12") (pin "P$2") (pinfunction "IN_P$2") (pintype "bidirectional"))
      (node (ref "IC14") (pin "5") (pinfunction "SD_5") (pintype "bidirectional"))
      (node (ref "IC14") (pin "7") (pinfunction "IN1_7") (pintype "bidirectional"))
      (node (ref "IC14") (pin "8") (pinfunction "IN2_8") (pintype "bidirectional"))
      (node (ref "IC7") (pin "3") (pinfunction "VIN_3") (pintype "input"))
      (node (ref "IC8") (pin "5") (pinfunction "SD_5") (pintype "bidirectional"))
      (node (ref "IC8") (pin "7") (pinfunction "IN1_7") (pintype "bidirectional"))
      (node (ref "IC8") (pin "8") (pinfunction "IN2_8") (pintype "bidirectional"))
      (node (ref "IC9") (pin "1") (pinfunction "IN+_1") (pintype "bidirectional"))
      (node (ref "J5") (pin "+") (pinfunction "+_+") (pintype "passive"))
      (node (ref "R47") (pin "2") (pinfunction "2_2") (pintype "passive"))
      (node (ref "TP2") (pin "1") (pinfunction "P$1_1") (pintype "bidirectional"))
    )
    (net (code "2") (name "/+15V") (class "Default")
      (node (ref "15V_EN") (pin "2") (pinfunction "2_2") (pintype "passive"))
      (node (ref "C32") (pin "2") (pinfunction "P$2_2") (pintype "passive"))
      (node (ref "C33") (pin "1") (pinfunction "P$1_1") (pintype "passive"))
      (node (ref "D2") (pin "C") (pinfunction "C_C") (pintype "passive"))
      (node (ref "IC10") (pin "3") (pinfunction "IN_3") (pintype "bidirectional"))
      (node (ref "R44") (pin "2") (pinfunction "2_2") (pintype "passive"))
      (node (ref "TP5") (pin "1") (pinfunction "P$1_1") (pintype "bidirectional"))
    )
    (net (code "3") (name "/-15V") (class "Default")
      (node (ref "15V_EN") (pin "4") (pinfunction "2_4") (pintype "passive"))
      (node (ref "C36") (pin "1") (pinfunction "P$1_1") (pintype "passive"))
      (node (ref "C37") (pin "2") (pinfunction "P$2_2") (pintype "passive"))
      (node (ref "D3") (pin "A") (pinfunction "A_A") (pintype "passive"))
      (node (ref "IC11") (pin "2") (pinfunction "IN_2") (pintype "bidirectional"))
      (node (ref "IC11") (pin "4") (pinfunction "IN_TAB_4") (pintype "bidirectional"))
      (node (ref "LED4") (pin "C") (pinfunction "C_C") (pintype "passive"))
      (node (ref "TP6") (pin "1") (pinfunction "P$1_1") (pintype "bidirectional"))
    )
    (net (code "4") (name "/DAC_VCC") (class "Default")
      (node (ref "C19") (pin "2") (pinfunction "P$2_2") (pintype "passive"))
      (node (ref "C21") (pin "2") (pinfunction "P$2_2") (pintype "passive"))
      (node (ref "C23") (pin "2") (pinfunction "P$2_2") (pintype "passive"))
      (node (ref "EN_DAC_VCC") (pin "2") (pinfunction "2_2") (pintype "passive"))
      (node (ref "L2") (pin "2") (pinfunction "2_2") (pintype "passive"))
      (node (ref "L3") (pin "2") (pinfunction "2_2") (pintype "passive"))
      (node (ref "L4") (pin "2") (pinfunction "2_2") (pintype "passive"))
      (node (ref "R45") (pin "2") (pinfunction "2_2") (pintype "passive"))
      (node (ref "TP3") (pin "1") (pinfunction "P$1_1") (pintype "bidirectional"))
    )
    (net (code "5") (name "/HP_VCC") (class "Default")
      (node (ref "C61") (pin "1") (pinfunction "P$1_1") (pintype "passive"))
      (node (ref "C66") (pin "1") (pinfunction "P$1_1") (pintype "passive"))
      (node (ref "C69") (pin "1") (pinfunction "P$1_1") (pintype "passive"))
      (node (ref "C70") (pin "1") (pinfunction "P$1_1") (pintype "passive"))
      (node (ref "HP_EN") (pin "2") (pinfunction "2_2") (pintype "passive"))
      (node (ref "IC13") (pin "1") (pinfunction "CPVDD_1") (pintype "bidirectional"))
      (node (ref "IC13") (pin "17") (pinfunction "XSMT_17") (pintype "bidirectional"))
      (node (ref "IC13") (pin "20") (pinfunction "DVDD_20") (pintype "bidirectional"))
      (node (ref "L8") (pin "1") (pinfunction "1_1") (pintype "passive"))
    )
    (net (code "6") (name "/I2S_BCK") (class "Default")
      (node (ref "IC1") (pin "6") (pinfunction "BCK_6") (pintype "bidirectional"))
      (node (ref "IC13") (pin "13") (pinfunction "BCK_13") (pintype "bidirectional"))
      (node (ref "SV1") (pin "7") (pinfunction "7_7") (pintype "passive"))
    )
    (net (code "7") (name "/I2S_DATA") (class "Default")
      (node (ref "IC1") (pin "5") (pinfunction "DATA_5") (pintype "bidirectional"))
      (node (ref "SV1") (pin "5") (pinfunction "5_5") (pintype "passive"))
    )
    (net (code "8") (name "/I2S_DATA2") (class "Default")
      (node (ref "IC13") (pin "14") (pinfunction "DIN_14") (pintype "bidirectional"))
      (node (ref "SV1") (pin "1") (pinfunction "1_1") (pintype "passive"))
    )
    (net (code "9") (name "/I2S_LRCK") (class "Default")
      (node (ref "IC1") (pin "4") (pinfunction "LRCK_4") (pintype "bidirectional"))
      (node (ref "IC13") (pin "15") (pinfunction "LRCK_15") (pintype "bidirectional"))
      (node (ref "SV1") (pin "3") (pinfunction "3_3") (pintype "passive"))
    )
    (net (code "10") (name "/I2S_MCK") (class "Default")
      (node (ref "IC1") (pin "7") (pinfunction "SCK_7") (pintype "bidirectional"))
      (node (ref "IC13") (pin "12") (pinfunction "SCK_12") (pintype "bidirectional"))
      (node (ref "R48") (pin "2") (pinfunction "2_2") (pintype "passive"))
      (node (ref "SV1") (pin "9") (pinfunction "9_9") (pintype "passive"))
      (node (ref "TP18") (pin "1") (pinfunction "P$1_1") (pintype "bidirectional"))
    )
    (net (code "11") (name "/IN_L_NN") (class "Default")
      (node (ref "IC2") (pin "1") (pinfunction "VIN-_1") (pintype "bidirectional"))
      (node (ref "JP1") (pin "7") (pinfunction "7_7") (pintype "passive"))
      (node (ref "R2") (pin "1") (pinfunction "1_1") (pintype "passive"))
      (node (ref "TP9") (pin "1") (pinfunction "P$1_1") (pintype "bidirectional"))
    )
    (net (code "12") (name "/IN_L_PP") (class "Default")
      (node (ref "IC2") (pin "8") (pinfunction "VIN+_8") (pintype "bidirectional"))
      (node (ref "JP1") (pin "5") (pinfunction "5_5") (pintype "passive"))
      (node (ref "R1") (pin "1") (pinfunction "1_1") (pintype "passive"))
      (node (ref "TP7") (pin "1") (pinfunction "P$1_1") (pintype "bidirectional"))
    )
    (net (code "13") (name "/IN_R_NN") (class "Default")
      (node (ref "IC4") (pin "1") (pinfunction "VIN-_1") (pintype "bidirectional"))
      (node (ref "JP1") (pin "3") (pinfunction "3_3") (pintype "passive"))
      (node (ref "R18") (pin "1") (pinfunction "1_1") (pintype "passive"))
      (node (ref "TP14") (pin "1") (pinfunction "P$1_1") (pintype "bidirectional"))
    )
    (net (code "14") (name "/IN_R_PP") (class "Default")
      (node (ref "IC4") (pin "8") (pinfunction "VIN+_8") (pintype "bidirectional"))
      (node (ref "JP1") (pin "1") (pinfunction "1_1") (pintype "passive"))
      (node (ref "R17") (pin "1") (pinfunction "1_1") (pintype "passive"))
      (node (ref "TP13") (pin "1") (pinfunction "P$1_1") (pintype "bidirectional"))
    )
    (net (code "15") (name "/SPI_CLK") (class "Default")
      (node (ref "IC1") (pin "12") (pinfunction "MC_12") (pintype "bidirectional"))
      (node (ref "SV1") (pin "17") (pinfunction "17_17") (pintype "passive"))
    )
    (net (code "16") (name "/SPI_CS") (class "Default")
      (node (ref "IC1") (pin "10") (pinfunction "MS_10") (pintype "bidirectional"))
      (node (ref "SV1") (pin "11") (pinfunction "11_11") (pintype "passive"))
    )
    (net (code "17") (name "/SPI_MISO") (class "Default")
      (node (ref "IC1") (pin "13") (pinfunction "MDO_13") (pintype "bidirectional"))
      (node (ref "SV1") (pin "15") (pinfunction "15_15") (pintype "passive"))
    )
    (net (code "18") (name "/SPI_MOSI") (class "Default")
      (node (ref "IC1") (pin "11") (pinfunction "MDI_11") (pintype "bidirectional"))
      (node (ref "SV1") (pin "13") (pinfunction "13_13") (pintype "passive"))
    )
    (net (code "19") (name "3.3V") (class "Default")
      (node (ref "C52") (pin "1") (pinfunction "P$1_1") (pintype "passive"))
      (node (ref "EN_3.3") (pin "2") (pinfunction "2_2") (pintype "passive"))
      (node (ref "L1") (pin "1") (pinfunction "1_1") (pintype "passive"))
      (node (ref "OSC1") (pin "4") (pinfunction "VCC_4") (pintype "power_in"))
      (node (ref "R34") (pin "1") (pinfunction "1_1") (pintype "passive"))
      (node (ref "R43") (pin "2") (pinfunction "2_2") (pintype "passive"))
      (node (ref "TP4") (pin "1") (pinfunction "P$1_1") (pintype "bidirectional"))
    )
    (net (code "20") (name "AVCC") (class "Default")
      (node (ref "APWR_EN") (pin "2") (pinfunction "2_2") (pintype "passive"))
      (node (ref "C12") (pin "1") (pinfunction "P$1_1") (pintype "passive"))
      (node (ref "C13") (pin "1") (pinfunction "P$1_1") (pintype "passive"))
      (node (ref "C15") (pin "+") (pinfunction "+_+") (pintype "passive"))
      (node (ref "C39") (pin "1") (pinfunction "P$1_1") (pintype "passive"))
      (node (ref "C4") (pin "1") (pinfunction "P$1_1") (pintype "passive"))
      (node (ref "C41") (pin "1") (pinfunction "P$1_1") (pintype "passive"))
      (node (ref "C43") (pin "1") (pinfunction "P$1_1") (pintype "passive"))
      (node (ref "C45") (pin "1") (pinfunction "P$1_1") (pintype "passive"))
      (node (ref "C47") (pin "1") (pinfunction "P$1_1") (pintype "passive"))
      (node (ref "C5") (pin "1") (pinfunction "P$1_1") (pintype "passive"))
      (node (ref "C50") (pin "1") (pinfunction "P$1_1") (pintype "passive"))
      (node (ref "C7") (pin "+") (pinfunction "+_+") (pintype "passive"))
      (node (ref "IC2") (pin "3") (pinfunction "V+_3") (pintype "bidirectional"))
      (node (ref "IC3") (pin "3") (pinfunction "V+_3") (pintype "bidirectional"))
      (node (ref "IC4") (pin "3") (pinfunction "V+_3") (pintype "bidirectional"))
      (node (ref "IC5") (pin "8") (pinfunction "V+_8") (pintype "power_in"))
      (node (ref "IC6") (pin "3") (pinfunction "V+_3") (pintype "bidirectional"))
    )
    (net (code "21") (name "AVDD") (class "Default")
      (node (ref "APWR_EN") (pin "4") (pinfunction "2_4") (pintype "passive"))
      (node (ref "C11") (pin "2") (pinfunction "P$2_2") (pintype "passive"))
      (node (ref "C14") (pin "2") (pinfunction "P$2_2") (pintype "passive"))
      (node (ref "C16") (pin "-") (pinfunction "-_-") (pintype "passive"))
      (node (ref "C3") (pin "2") (pinfunction "P$2_2") (pintype "passive"))
      (node (ref "C40") (pin "2") (pinfunction "P$2_2") (pintype "passive"))
      (node (ref "C42") (pin "2") (pinfunction "P$2_2") (pintype "passive"))
      (node (ref "C44") (pin "2") (pinfunction "P$2_2") (pintype "passive"))
      (node (ref "C46") (pin "2") (pinfunction "P$2_2") (pintype "passive"))
      (node (ref "C48") (pin "2") (pinfunction "P$2_2") (pintype "passive"))
      (node (ref "C49") (pin "2") (pinfunction "P$2_2") (pintype "passive"))
      (node (ref "C6") (pin "2") (pinfunction "P$2_2") (pintype "passive"))
      (node (ref "C8") (pin "-") (pinfunction "-_-") (pintype "passive"))
      (node (ref "IC2") (pin "6") (pinfunction "V-_6") (pintype "bidirectional"))
      (node (ref "IC3") (pin "6") (pinfunction "V-_6") (pintype "bidirectional"))
      (node (ref "IC4") (pin "6") (pinfunction "V-_6") (pintype "bidirectional"))
      (node (ref "IC5") (pin "4") (pinfunction "V-_4") (pintype "power_in"))
      (node (ref "IC6") (pin "6") (pinfunction "V-_6") (pintype "bidirectional"))
    )
    (net (code "22") (name "GND") (class "Default")
      (node (ref "C1") (pin "2") (pinfunction "P$2_2") (pintype "passive"))
      (node (ref "C10") (pin "1") (pinfunction "P$1_1") (pintype "passive"))
      (node (ref "C11") (pin "1") (pinfunction "P$1_1") (pintype "passive"))
      (node (ref "C12") (pin "2") (pinfunction "P$2_2") (pintype "passive"))
      (node (ref "C13") (pin "2") (pinfunction "P$2_2") (pintype "passive"))
      (node (ref "C14") (pin "1") (pinfunction "P$1_1") (pintype "passive"))
      (node (ref "C15") (pin "-") (pinfunction "-_-") (pintype "passive"))
      (node (ref "C16") (pin "+") (pinfunction "+_+") (pintype "passive"))
      (node (ref "C17") (pin "2") (pinfunction "P$2_2") (pintype "passive"))
      (node (ref "C18") (pin "2") (pinfunction "P$2_2") (pintype "passive"))
      (node (ref "C19") (pin "1") (pinfunction "P$1_1") (pintype "passive"))
      (node (ref "C2") (pin "1") (pinfunction "P$1_1") (pintype "passive"))
      (node (ref "C20") (pin "2") (pinfunction "P$2_2") (pintype "passive"))
      (node (ref "C21") (pin "1") (pinfunction "P$1_1") (pintype "passive"))
      (node (ref "C22") (pin "2") (pinfunction "P$2_2") (pintype "passive"))
      (node (ref "C23") (pin "1") (pinfunction "P$1_1") (pintype "passive"))
      (node (ref "C26") (pin "-") (pinfunction "-_-") (pintype "passive"))
      (node (ref "C27") (pin "2") (pinfunction "P$2_2") (pintype "passive"))
      (node (ref "C28") (pin "2") (pinfunction "P$2_2") (pintype "passive"))
      (node (ref "C29") (pin "1") (pinfunction "P$1_1") (pintype "passive"))
      (node (ref "C3") (pin "1") (pinfunction "P$1_1") (pintype "passive"))
      (node (ref "C30") (pin "2-") (pinfunction "-_2-") (pintype "passive"))
      (node (ref "C31") (pin "1+") (pinfunction "+_1+") (pintype "passive"))
      (node (ref "C32") (pin "1") (pinfunction "P$1_1") (pintype "passive"))
      (node (ref "C33") (pin "2") (pinfunction "P$2_2") (pintype "passive"))
      (node (ref "C34") (pin "2") (pinfunction "P$2_2") (pintype "passive"))
      (node (ref "C35") (pin "2") (pinfunction "P$2_2") (pintype "passive"))
      (node (ref "C36") (pin "2") (pinfunction "P$2_2") (pintype "passive"))
      (node (ref "C37") (pin "1") (pinfunction "P$1_1") (pintype "passive"))
      (node (ref "C38") (pin "1") (pinfunction "P$1_1") (pintype "passive"))
      (node (ref "C39") (pin "2") (pinfunction "P$2_2") (pintype "passive"))
      (node (ref "C4") (pin "2") (pinfunction "P$2_2") (pintype "passive"))
      (node (ref "C40") (pin "1") (pinfunction "P$1_1") (pintype "passive"))
      (node (ref "C41") (pin "2") (pinfunction "P$2_2") (pintype "passive"))
      (node (ref "C42") (pin "1") (pinfunction "P$1_1") (pintype "passive"))
      (node (ref "C43") (pin "2") (pinfunction "P$2_2") (pintype "passive"))
      (node (ref "C44") (pin "1") (pinfunction "P$1_1") (pintype "passive"))
      (node (ref "C45") (pin "2") (pinfunction "P$2_2") (pintype "passive"))
      (node (ref "C46") (pin "1") (pinfunction "P$1_1") (pintype "passive"))
      (node (ref "C47") (pin "2") (pinfunction "P$2_2") (pintype "passive"))
      (node (ref "C48") (pin "1") (pinfunction "P$1_1") (pintype "passive"))
      (node (ref "C49") (pin "1") (pinfunction "P$1_1") (pintype "passive"))
      (node (ref "C5") (pin "2") (pinfunction "P$2_2") (pintype "passive"))
      (node (ref "C50") (pin "2") (pinfunction "P$2_2") (pintype "passive"))
      (node (ref "C51") (pin "1") (pinfunction "P$1_1") (pintype "passive"))
      (node (ref "C52") (pin "2") (pinfunction "P$2_2") (pintype "passive"))
      (node (ref "C53") (pin "1") (pinfunction "P$1_1") (pintype "passive"))
      (node (ref "C55") (pin "1") (pinfunction "P$1_1") (pintype "passive"))
      (node (ref "C56") (pin "2") (pinfunction "P$2_2") (pintype "passive"))
      (node (ref "C57") (pin "2") (pinfunction "P$2_2") (pintype "passive"))
      (node (ref "C58") (pin "2") (pinfunction "P$2_2") (pintype "passive"))
      (node (ref "C59") (pin "2") (pinfunction "P$2_2") (pintype "passive"))
      (node (ref "C6") (pin "1") (pinfunction "P$1_1") (pintype "passive"))
      (node (ref "C60") (pin "2") (pinfunction "P$2_2") (pintype "passive"))
      (node (ref "C61") (pin "2") (pinfunction "P$2_2") (pintype "passive"))
      (node (ref "C62") (pin "2") (pinfunction "P$2_2") (pintype "passive"))
      (node (ref "C63") (pin "1") (pinfunction "P$1_1") (pintype "passive"))
      (node (ref "C64") (pin "2") (pinfunction "P$2_2") (pintype "passive"))
      (node (ref "C65") (pin "2") (pinfunction "P$2_2") (pintype "passive"))
      (node (ref "C66") (pin "2") (pinfunction "P$2_2") (pintype "passive"))
      (node (ref "C67") (pin "1") (pinfunction "P$1_1") (pintype "passive"))
      (node (ref "C68") (pin "1") (pinfunction "P$1_1") (pintype "passive"))
      (node (ref "C69") (pin "2") (pinfunction "P$2_2") (pintype "passive"))
      (node (ref "C7") (pin "-") (pinfunction "-_-") (pintype "passive"))
      (node (ref "C70") (pin "2") (pinfunction "P$2_2") (pintype "passive"))
      (node (ref "C72") (pin "1") (pinfunction "P$1_1") (pintype "passive"))
      (node (ref "C73") (pin "2") (pinfunction "P$2_2") (pintype "passive"))
      (node (ref "C74") (pin "1") (pinfunction "P$1_1") (pintype "passive"))
      (node (ref "C75") (pin "1") (pinfunction "P$1_1") (pintype "passive"))
      (node (ref "C77") (pin "1") (pinfunction "P$1_1") (pintype "passive"))
      (node (ref "C8") (pin "+") (pinfunction "+_+") (pintype "passive"))
      (node (ref "C9") (pin "2") (pinfunction "P$2_2") (pintype "passive"))
      (node (ref "HP") (pin "P$2") (pinfunction "1_P$2") (pintype "passive"))
      (node (ref "IC1") (pin "16") (pinfunction "AGND3R_16") (pintype "bidirectional"))
      (node (ref "IC1") (pin "19") (pinfunction "AGND1_19") (pintype "bidirectional"))
      (node (ref "IC1") (pin "24") (pinfunction "AGND2_24") (pintype "bidirectional"))
      (node (ref "IC1") (pin "27") (pinfunction "AGND3L_27") (pintype "bidirectional"))
      (node (ref "IC1") (pin "3") (pinfunction "MSEL_3") (pintype "bidirectional"))
      (node (ref "IC1") (pin "8") (pinfunction "DGND_8") (pintype "bidirectional"))
      (node (ref "IC12") (pin "P$3") (pinfunction "GND_P$3") (pintype "bidirectional"))
      (node (ref "IC13") (pin "10") (pinfunction "DEMP_10") (pintype "bidirectional"))
      (node (ref "IC13") (pin "11") (pinfunction "FLT_11") (pintype "bidirectional"))
      (node (ref "IC13") (pin "16") (pinfunction "FMT_16") (pintype "bidirectional"))
      (node (ref "IC13") (pin "19") (pinfunction "DGND_19") (pintype "bidirectional"))
      (node (ref "IC13") (pin "3") (pinfunction "CPGND_3") (pintype "bidirectional"))
      (node (ref "IC13") (pin "9") (pinfunction "AGND_9") (pintype "bidirectional"))
      (node (ref "IC14") (pin "4") (pinfunction "GND_4") (pintype "bidirectional"))
      (node (ref "IC2") (pin "2") (pinfunction "VCOM_2") (pintype "bidirectional"))
      (node (ref "IC2") (pin "7") (pinfunction "ENABLE_7") (pintype "bidirectional"))
      (node (ref "IC3") (pin "2") (pinfunction "VCOM_2") (pintype "bidirectional"))
      (node (ref "IC3") (pin "7") (pinfunction "ENABLE_7") (pintype "bidirectional"))
      (node (ref "IC4") (pin "2") (pinfunction "VCOM_2") (pintype "bidirectional"))
      (node (ref "IC4") (pin "7") (pinfunction "ENABLE_7") (pintype "bidirectional"))
      (node (ref "IC6") (pin "2") (pinfunction "VCOM_2") (pintype "bidirectional"))
      (node (ref "IC6") (pin "7") (pinfunction "ENABLE_7") (pintype "bidirectional"))
      (node (ref "IC7") (pin "1") (pinfunction "GND_1") (pintype "power_in"))
      (node (ref "IC8") (pin "4") (pinfunction "GND_4") (pintype "bidirectional"))
      (node (ref "IC9") (pin "2") (pinfunction "IN-_2") (pintype "bidirectional"))
      (node (ref "IC9") (pin "6") (pinfunction "GND_6") (pintype "bidirectional"))
      (node (ref "J1") (pin "L_GND") (pinfunction "L_GND_L_GND") (pintype "passive"))
      (node (ref "J1") (pin "R_GND") (pinfunction "R_GND_R_GND") (pintype "passive"))
      (node (ref "J5") (pin "-") (pinfunction "-_-") (pintype "passive"))
      (node (ref "LED1") (pin "C") (pinfunction "C_C") (pintype "passive"))
      (node (ref "LED2") (pin "C") (pinfunction "C_C") (pintype "passive"))
      (node (ref "LED3") (pin "C") (pinfunction "C_C") (pintype "passive"))
      (node (ref "LED5") (pin "C") (pinfunction "C_C") (pintype "passive"))
      (node (ref "OSC1") (pin "2") (pinfunction "GND_2") (pintype "power_in"))
      (node (ref "R11") (pin "2") (pinfunction "2_2") (pintype "passive"))
      (node (ref "R16") (pin "1") (pinfunction "1_1") (pintype "passive"))
      (node (ref "R27") (pin "2") (pinfunction "2_2") (pintype "passive"))
      (node (ref "R32") (pin "1") (pinfunction "1_1") (pintype "passive"))
      (node (ref "R33") (pin "2") (pinfunction "2_2") (pintype "passive"))
      (node (ref "R40") (pin "1") (pinfunction "1_1") (pintype "passive"))
      (node (ref "R41") (pin "2") (pinfunction "2_2") (pintype "passive"))
      (node (ref "R46") (pin "2") (pinfunction "2_2") (pintype "passive"))
      (node (ref "R49") (pin "2") (pinfunction "2_2") (pintype "passive"))
      (node (ref "SV1") (pin "10") (pinfunction "10_10") (pintype "passive"))
      (node (ref "SV1") (pin "12") (pinfunction "12_12") (pintype "passive"))
      (node (ref "SV1") (pin "14") (pinfunction "14_14") (pintype "passive"))
      (node (ref "SV1") (pin "16") (pinfunction "16_16") (pintype "passive"))
      (node (ref "SV1") (pin "18") (pinfunction "18_18") (pintype "passive"))
      (node (ref "SV1") (pin "19") (pinfunction "19_19") (pintype "passive"))
      (node (ref "SV1") (pin "2") (pinfunction "2_2") (pintype "passive"))
      (node (ref "SV1") (pin "20") (pinfunction "20_20") (pintype "passive"))
      (node (ref "SV1") (pin "4") (pinfunction "4_4") (pintype "passive"))
      (node (ref "SV1") (pin "6") (pinfunction "6_6") (pintype "passive"))
      (node (ref "SV1") (pin "8") (pinfunction "8_8") (pintype "passive"))
      (node (ref "TP1") (pin "1") (pinfunction "P$1_1") (pintype "bidirectional"))
      (node (ref "TP19") (pin "1") (pinfunction "P$1_1") (pintype "bidirectional"))
      (node (ref "TP20") (pin "1") (pinfunction "P$1_1") (pintype "bidirectional"))
      (node (ref "TP8") (pin "1") (pinfunction "P$1_1") (pintype "bidirectional"))
      (node (ref "X1") (pin "P$4") (pinfunction "1_P$4") (pintype "passive"))
      (node (ref "X2") (pin "P$4") (pinfunction "1_P$4") (pintype "passive"))
    )
    (net (code "23") (name "Net-(15V_ENB-1)") (class "Default")
      (node (ref "15V_EN") (pin "3") (pinfunction "1_3") (pintype "passive"))
      (node (ref "C29") (pin "2") (pinfunction "P$2_2") (pintype "passive"))
      (node (ref "C31") (pin "2-") (pinfunction "-_2-") (pintype "passive"))
      (node (ref "IC9") (pin "5") (pinfunction "OUT-_5") (pintype "bidirectional"))
    )
    (net (code "24") (name "Net-(APWR_EN-Pad1)") (class "Default")
      (node (ref "APWR_EN") (pin "1") (pinfunction "1_1") (pintype "passive"))
      (node (ref "L5") (pin "2") (pinfunction "2_2") (pintype "passive"))
    )
    (net (code "25") (name "Net-(APWR_ENB-1)") (class "Default")
      (node (ref "APWR_EN") (pin "3") (pinfunction "1_3") (pintype "passive"))
      (node (ref "L6") (pin "2") (pinfunction "2_2") (pintype "passive"))
    )
    (net (code "26") (name "Net-(BAL_LEFT-PadS)") (class "Default")
      (node (ref "BAL_LEFT") (pin "S") (pinfunction "S_S") (pintype "passive"))
      (node (ref "R16") (pin "2") (pinfunction "2_2") (pintype "passive"))
    )
    (net (code "27") (name "Net-(BAL_RIGHT-PadS)") (class "Default")
      (node (ref "BAL_RIGHT") (pin "S") (pinfunction "S_S") (pintype "passive"))
      (node (ref "R32") (pin "2") (pinfunction "2_2") (pintype "passive"))
    )
    (net (code "28") (name "Net-(C1-P$1)") (class "Default")
      (node (ref "C1") (pin "1") (pinfunction "P$1_1") (pintype "passive"))
      (node (ref "R3") (pin "2") (pinfunction "2_2") (pintype "passive"))
      (node (ref "R4") (pin "1") (pinfunction "1_1") (pintype "passive"))
    )
    (net (code "29") (name "Net-(C2-P$2)") (class "Default")
      (node (ref "C2") (pin "2") (pinfunction "P$2_2") (pintype "passive"))
      (node (ref "R5") (pin "2") (pinfunction "2_2") (pintype "passive"))
      (node (ref "R6") (pin "1") (pinfunction "1_1") (pintype "passive"))
    )
    (net (code "30") (name "Net-(C9-P$1)") (class "Default")
      (node (ref "C9") (pin "1") (pinfunction "P$1_1") (pintype "passive"))
      (node (ref "R19") (pin "2") (pinfunction "2_2") (pintype "passive"))
      (node (ref "R20") (pin "1") (pinfunction "1_1") (pintype "passive"))
    )
    (net (code "31") (name "Net-(C10-P$2)") (class "Default")
      (node (ref "C10") (pin "2") (pinfunction "P$2_2") (pintype "passive"))
      (node (ref "R21") (pin "2") (pinfunction "2_2") (pintype "passive"))
      (node (ref "R22") (pin "1") (pinfunction "1_1") (pintype "passive"))
    )
    (net (code "32") (name "Net-(C17-P$1)") (class "Default")
      (node (ref "C17") (pin "1") (pinfunction "P$1_1") (pintype "passive"))
      (node (ref "IC1") (pin "9") (pinfunction "VDD_9") (pintype "bidirectional"))
      (node (ref "L1") (pin "2") (pinfunction "2_2") (pintype "passive"))
    )
    (net (code "33") (name "Net-(C18-P$1)") (class "Default")
      (node (ref "C18") (pin "1") (pinfunction "P$1_1") (pintype "passive"))
      (node (ref "IC1") (pin "15") (pinfunction "VCC2R_15") (pintype "bidirectional"))
      (node (ref "L2") (pin "1") (pinfunction "1_1") (pintype "passive"))
    )
    (net (code "34") (name "Net-(C20-P$1)") (class "Default")
      (node (ref "C20") (pin "1") (pinfunction "P$1_1") (pintype "passive"))
      (node (ref "IC1") (pin "28") (pinfunction "VCC2L_28") (pintype "bidirectional"))
      (node (ref "L3") (pin "1") (pinfunction "1_1") (pintype "passive"))
    )
    (net (code "35") (name "Net-(C22-P$1)") (class "Default")
      (node (ref "C22") (pin "1") (pinfunction "P$1_1") (pintype "passive"))
      (node (ref "C24") (pin "+") (pinfunction "+_+") (pintype "passive"))
      (node (ref "C25") (pin "+") (pinfunction "+_+") (pintype "passive"))
      (node (ref "IC1") (pin "23") (pinfunction "VCC1_23") (pintype "bidirectional"))
      (node (ref "L4") (pin "1") (pinfunction "1_1") (pintype "passive"))
    )
    (net (code "36") (name "Net-(C28-P$1)") (class "Default")
      (node (ref "15V_EN") (pin "1") (pinfunction "1_1") (pintype "passive"))
      (node (ref "C28") (pin "1") (pinfunction "P$1_1") (pintype "passive"))
      (node (ref "C30") (pin "1+") (pinfunction "+_1+") (pintype "passive"))
      (node (ref "IC9") (pin "7") (pinfunction "OUT+_7") (pintype "bidirectional"))
    )
    (net (code "37") (name "Net-(C34-P$1)") (class "Default")
      (node (ref "C34") (pin "1") (pinfunction "P$1_1") (pintype "passive"))
      (node (ref "D1") (pin "A") (pinfunction "A_A") (pintype "passive"))
      (node (ref "IC10") (pin "1") (pinfunction "ADJ_1") (pintype "bidirectional"))
      (node (ref "R39") (pin "1") (pinfunction "1_1") (pintype "passive"))
      (node (ref "R40") (pin "2") (pinfunction "2_2") (pintype "passive"))
    )
    (net (code "38") (name "Net-(C35-P$1)") (class "Default")
      (node (ref "C35") (pin "1") (pinfunction "P$1_1") (pintype "passive"))
      (node (ref "D1") (pin "C") (pinfunction "C_C") (pintype "passive"))
      (node (ref "D2") (pin "A") (pinfunction "A_A") (pintype "passive"))
      (node (ref "IC10") (pin "2") (pinfunction "OUT_2") (pintype "bidirectional"))
      (node (ref "IC10") (pin "4") (pinfunction "OUT_TAB_4") (pintype "bidirectional"))
      (node (ref "L5") (pin "1") (pinfunction "1_1") (pintype "passive"))
      (node (ref "R39") (pin "2") (pinfunction "2_2") (pintype "passive"))
    )
    (net (code "39") (name "Net-(C38-P$2)") (class "Default")
      (node (ref "C38") (pin "2") (pinfunction "P$2_2") (pintype "passive"))
      (node (ref "D4") (pin "C") (pinfunction "C_C") (pintype "passive"))
      (node (ref "IC11") (pin "1") (pinfunction "ADJ_1") (pintype "bidirectional"))
      (node (ref "R41") (pin "1") (pinfunction "1_1") (pintype "passive"))
      (node (ref "R42") (pin "2") (pinfunction "2_2") (pintype "passive"))
    )
    (net (code "40") (name "Net-(C51-P$2)") (class "Default")
      (node (ref "C51") (pin "2") (pinfunction "P$2_2") (pintype "passive"))
      (node (ref "D3") (pin "C") (pinfunction "C_C") (pintype "passive"))
      (node (ref "D4") (pin "A") (pinfunction "A_A") (pintype "passive"))
      (node (ref "IC11") (pin "3") (pinfunction "OUT_3") (pintype "bidirectional"))
      (node (ref "L6") (pin "1") (pinfunction "1_1") (pintype "passive"))
      (node (ref "R42") (pin "1") (pinfunction "1_1") (pintype "passive"))
    )
    (net (code "41") (name "Net-(C54-P$1)") (class "Default")
      (node (ref "C54") (pin "1") (pinfunction "P$1_1") (pintype "passive"))
      (node (ref "IC8") (pin "3") (pinfunction "NR_3") (pintype "bidirectional"))
    )
    (net (code "42") (name "Net-(C54-P$2)") (class "Default")
      (node (ref "C54") (pin "2") (pinfunction "P$2_2") (pintype "passive"))
      (node (ref "C55") (pin "2") (pinfunction "P$2_2") (pintype "passive"))
      (node (ref "EN_3.3") (pin "1") (pinfunction "1_1") (pintype "passive"))
      (node (ref "IC8") (pin "1") (pinfunction "OUT1_1") (pintype "bidirectional"))
      (node (ref "IC8") (pin "2") (pinfunction "OUT2_2") (pintype "bidirectional"))
    )
    (net (code "43") (name "Net-(C56-P$1)") (class "Default")
      (node (ref "C56") (pin "1") (pinfunction "P$1_1") (pintype "passive"))
      (node (ref "C57") (pin "1") (pinfunction "P$1_1") (pintype "passive"))
      (node (ref "IC12") (pin "P$4") (pinfunction "OUT_P$4") (pintype "bidirectional"))
      (node (ref "X1") (pin "P$1") (pinfunction "1_P$1") (pintype "passive"))
      (node (ref "X2") (pin "P$1") (pinfunction "1_P$1") (pintype "passive"))
    )
    (net (code "44") (name "Net-(C59-P$1)") (class "Default")
      (node (ref "C59") (pin "1") (pinfunction "P$1_1") (pintype "passive"))
      (node (ref "C60") (pin "1") (pinfunction "P$1_1") (pintype "passive"))
      (node (ref "IC13") (pin "8") (pinfunction "AVDD_8") (pintype "bidirectional"))
      (node (ref "L8") (pin "2") (pinfunction "2_2") (pintype "passive"))
    )
    (net (code "45") (name "Net-(C64-P$1)") (class "Default")
      (node (ref "C64") (pin "1") (pinfunction "P$1_1") (pintype "passive"))
      (node (ref "C65") (pin "1") (pinfunction "P$1_1") (pintype "passive"))
      (node (ref "EN_DAC_VCC") (pin "1") (pinfunction "1_1") (pintype "passive"))
      (node (ref "IC7") (pin "2") (pinfunction "VOUT_2") (pintype "output"))
      (node (ref "IC7") (pin "4") (pinfunction "VOUT_TAB_4") (pintype "output"))
    )
    (net (code "46") (name "Net-(C67-P$2)") (class "Default")
      (node (ref "C67") (pin "2") (pinfunction "P$2_2") (pintype "passive"))
      (node (ref "C68") (pin "2") (pinfunction "P$2_2") (pintype "passive"))
      (node (ref "IC13") (pin "18") (pinfunction "LDOO_18") (pintype "bidirectional"))
    )
    (net (code "47") (name "Net-(C71-P$1)") (class "Default")
      (node (ref "C71") (pin "1") (pinfunction "P$1_1") (pintype "passive"))
      (node (ref "IC13") (pin "2") (pinfunction "CAPP_2") (pintype "bidirectional"))
    )
    (net (code "48") (name "Net-(C71-P$2)") (class "Default")
      (node (ref "C71") (pin "2") (pinfunction "P$2_2") (pintype "passive"))
      (node (ref "IC13") (pin "4") (pinfunction "CAPM_4") (pintype "bidirectional"))
    )
    (net (code "49") (name "Net-(C72-P$2)") (class "Default")
      (node (ref "C72") (pin "2") (pinfunction "P$2_2") (pintype "passive"))
      (node (ref "IC13") (pin "5") (pinfunction "VNEG_5") (pintype "bidirectional"))
    )
    (net (code "50") (name "Net-(C73-P$1)") (class "Default")
      (node (ref "C73") (pin "1") (pinfunction "P$1_1") (pintype "passive"))
      (node (ref "HP") (pin "P$4") (pinfunction "1_P$4") (pintype "passive"))
      (node (ref "R35") (pin "1") (pinfunction "1_1") (pintype "passive"))
    )
    (net (code "51") (name "Net-(C74-P$2)") (class "Default")
      (node (ref "C74") (pin "2") (pinfunction "P$2_2") (pintype "passive"))
      (node (ref "HP") (pin "P$3") (pinfunction "1_P$3") (pintype "passive"))
      (node (ref "R36") (pin "1") (pinfunction "1_1") (pintype "passive"))
    )
    (net (code "52") (name "Net-(C76-P$1)") (class "Default")
      (node (ref "C76") (pin "1") (pinfunction "P$1_1") (pintype "passive"))
      (node (ref "IC14") (pin "3") (pinfunction "NR_3") (pintype "bidirectional"))
    )
    (net (code "53") (name "Net-(C76-P$2)") (class "Default")
      (node (ref "C76") (pin "2") (pinfunction "P$2_2") (pintype "passive"))
      (node (ref "C77") (pin "2") (pinfunction "P$2_2") (pintype "passive"))
      (node (ref "HP_EN") (pin "1") (pinfunction "1_1") (pintype "passive"))
      (node (ref "IC14") (pin "1") (pinfunction "OUT1_1") (pintype "bidirectional"))
      (node (ref "IC14") (pin "2") (pinfunction "OUT2_2") (pintype "bidirectional"))
    )
    (net (code "54") (name "Net-(IC1-IOUT_LEFT_N)") (class "Default")
      (node (ref "IC1") (pin "26") (pinfunction "IOUT_LEFT_N_26") (pintype "bidirectional"))
      (node (ref "JP1") (pin "8") (pinfunction "8_8") (pintype "passive"))
    )
    (net (code "55") (name "Net-(IC1-IOUT_LEFT_P)") (class "Default")
      (node (ref "IC1") (pin "25") (pinfunction "IOUT_LEFT_P_25") (pintype "bidirectional"))
      (node (ref "JP1") (pin "6") (pinfunction "6_6") (pintype "passive"))
    )
    (net (code "56") (name "Net-(IC1-IOUT_RIGHT_N)") (class "Default")
      (node (ref "IC1") (pin "18") (pinfunction "IOUT_RIGHT_N_18") (pintype "bidirectional"))
      (node (ref "JP1") (pin "4") (pinfunction "4_4") (pintype "passive"))
    )
    (net (code "57") (name "Net-(IC1-IOUT_RIGHT_P)") (class "Default")
      (node (ref "IC1") (pin "17") (pinfunction "IOUT_RIGHT_P_17") (pintype "bidirectional"))
      (node (ref "JP1") (pin "2") (pinfunction "2_2") (pintype "passive"))
    )
    (net (code "58") (name "Net-(IC1-IREF)") (class "Default")
      (node (ref "IC1") (pin "20") (pinfunction "IREF_20") (pintype "bidirectional"))
      (node (ref "R33") (pin "1") (pinfunction "1_1") (pintype "passive"))
    )
    (net (code "59") (name "Net-(IC1-RST)") (class "Default")
      (node (ref "IC1") (pin "14") (pinfunction "RST_14") (pintype "bidirectional"))
      (node (ref "R34") (pin "2") (pinfunction "2_2") (pintype "passive"))
    )
    (net (code "60") (name "Net-(IC1-VCOM_LEFT)") (class "Default")
      (node (ref "C24") (pin "-") (pinfunction "-_-") (pintype "passive"))
      (node (ref "IC1") (pin "22") (pinfunction "VCOM_LEFT_22") (pintype "bidirectional"))
    )
    (net (code "61") (name "Net-(IC1-VCOM_RIGHT)") (class "Default")
      (node (ref "C25") (pin "-") (pinfunction "-_-") (pintype "passive"))
      (node (ref "IC1") (pin "21") (pinfunction "VCOM_RIGHT_21") (pintype "bidirectional"))
    )
    (net (code "62") (name "Net-(IC2-VOUT+)") (class "Default")
      (node (ref "IC2") (pin "4") (pinfunction "VOUT+_4") (pintype "bidirectional"))
      (node (ref "R2") (pin "2") (pinfunction "2_2") (pintype "passive"))
      (node (ref "R5") (pin "1") (pinfunction "1_1") (pintype "passive"))
    )
    (net (code "63") (name "Net-(IC2-VOUT-)") (class "Default")
      (node (ref "IC2") (pin "5") (pinfunction "VOUT-_5") (pintype "bidirectional"))
      (node (ref "R1") (pin "2") (pinfunction "2_2") (pintype "passive"))
      (node (ref "R3") (pin "1") (pinfunction "1_1") (pintype "passive"))
    )
    (net (code "64") (name "Net-(IC3-VIN+)") (class "Default")
      (node (ref "IC3") (pin "8") (pinfunction "VIN+_8") (pintype "bidirectional"))
      (node (ref "R4") (pin "2") (pinfunction "2_2") (pintype "passive"))
      (node (ref "R8") (pin "1") (pinfunction "1_1") (pintype "passive"))
    )
    (net (code "65") (name "Net-(IC3-VIN-)") (class "Default")
      (node (ref "IC3") (pin "1") (pinfunction "VIN-_1") (pintype "bidirectional"))
      (node (ref "R6") (pin "2") (pinfunction "2_2") (pintype "passive"))
      (node (ref "R7") (pin "1") (pinfunction "1_1") (pintype "passive"))
    )
    (net (code "66") (name "Net-(IC3-VOUT+)") (class "Default")
      (node (ref "IC3") (pin "4") (pinfunction "VOUT+_4") (pintype "bidirectional"))
      (node (ref "R10") (pin "1") (pinfunction "1_1") (pintype "passive"))
      (node (ref "R15") (pin "1") (pinfunction "1_1") (pintype "passive"))
      (node (ref "R7") (pin "2") (pinfunction "2_2") (pintype "passive"))
    )
    (net (code "67") (name "Net-(IC3-VOUT-)") (class "Default")
      (node (ref "IC3") (pin "5") (pinfunction "VOUT-_5") (pintype "bidirectional"))
      (node (ref "R14") (pin "1") (pinfunction "1_1") (pintype "passive"))
      (node (ref "R8") (pin "2") (pinfunction "2_2") (pintype "passive"))
      (node (ref "R9") (pin "1") (pinfunction "1_1") (pintype "passive"))
    )
    (net (code "68") (name "Net-(IC4-VOUT+)") (class "Default")
      (node (ref "IC4") (pin "4") (pinfunction "VOUT+_4") (pintype "bidirectional"))
      (node (ref "R18") (pin "2") (pinfunction "2_2") (pintype "passive"))
      (node (ref "R21") (pin "1") (pinfunction "1_1") (pintype "passive"))
    )
    (net (code "69") (name "Net-(IC4-VOUT-)") (class "Default")
      (node (ref "IC4") (pin "5") (pinfunction "VOUT-_5") (pintype "bidirectional"))
      (node (ref "R17") (pin "2") (pinfunction "2_2") (pintype "passive"))
      (node (ref "R19") (pin "1") (pinfunction "1_1") (pintype "passive"))
    )
    (net (code "70") (name "Net-(IC5A-+IN)") (class "Default")
      (node (ref "IC5") (pin "3") (pinfunction "+IN_3") (pintype "input"))
      (node (ref "R25") (pin "2") (pinfunction "2_2") (pintype "passive"))
      (node (ref "R27") (pin "1") (pinfunction "1_1") (pintype "passive"))
    )
    (net (code "71") (name "Net-(IC5A--IN)") (class "Default")
      (node (ref "IC5") (pin "2") (pinfunction "-IN_2") (pintype "input"))
      (node (ref "R26") (pin "2") (pinfunction "2_2") (pintype "passive"))
      (node (ref "R28") (pin "1") (pinfunction "1_1") (pintype "passive"))
    )
    (net (code "72") (name "Net-(IC5A-OUT)") (class "Default")
      (node (ref "IC5") (pin "1") (pinfunction "OUT_1") (pintype "output"))
      (node (ref "R28") (pin "2") (pinfunction "2_2") (pintype "passive"))
      (node (ref "R29") (pin "1") (pinfunction "1_1") (pintype "passive"))
    )
    (net (code "73") (name "Net-(IC5B-+IN)") (class "Default")
      (node (ref "IC5") (pin "5") (pinfunction "+IN_5") (pintype "input"))
      (node (ref "R11") (pin "1") (pinfunction "1_1") (pintype "passive"))
      (node (ref "R9") (pin "2") (pinfunction "2_2") (pintype "passive"))
    )
    (net (code "74") (name "Net-(IC5B--IN)") (class "Default")
      (node (ref "IC5") (pin "6") (pinfunction "-IN_6") (pintype "input"))
      (node (ref "R10") (pin "2") (pinfunction "2_2") (pintype "passive"))
      (node (ref "R12") (pin "1") (pinfunction "1_1") (pintype "passive"))
    )
    (net (code "75") (name "Net-(IC5B-OUT)") (class "Default")
      (node (ref "IC5") (pin "7") (pinfunction "OUT_7") (pintype "output"))
      (node (ref "R12") (pin "2") (pinfunction "2_2") (pintype "passive"))
      (node (ref "R13") (pin "1") (pinfunction "1_1") (pintype "passive"))
    )
    (net (code "76") (name "Net-(IC6-VIN+)") (class "Default")
      (node (ref "IC6") (pin "8") (pinfunction "VIN+_8") (pintype "bidirectional"))
      (node (ref "R20") (pin "2") (pinfunction "2_2") (pintype "passive"))
      (node (ref "R24") (pin "1") (pinfunction "1_1") (pintype "passive"))
    )
    (net (code "77") (name "Net-(IC6-VIN-)") (class "Default")
      (node (ref "IC6") (pin "1") (pinfunction "VIN-_1") (pintype "bidirectional"))
      (node (ref "R22") (pin "2") (pinfunction "2_2") (pintype "passive"))
      (node (ref "R23") (pin "1") (pinfunction "1_1") (pintype "passive"))
    )
    (net (code "78") (name "Net-(IC6-VOUT+)") (class "Default")
      (node (ref "IC6") (pin "4") (pinfunction "VOUT+_4") (pintype "bidirectional"))
      (node (ref "R23") (pin "2") (pinfunction "2_2") (pintype "passive"))
      (node (ref "R26") (pin "1") (pinfunction "1_1") (pintype "passive"))
      (node (ref "R31") (pin "1") (pinfunction "1_1") (pintype "passive"))
    )
    (net (code "79") (name "Net-(IC6-VOUT-)") (class "Default")
      (node (ref "IC6") (pin "5") (pinfunction "VOUT-_5") (pintype "bidirectional"))
      (node (ref "R24") (pin "2") (pinfunction "2_2") (pintype "passive"))
      (node (ref "R25") (pin "1") (pinfunction "1_1") (pintype "passive"))
      (node (ref "R30") (pin "1") (pinfunction "1_1") (pintype "passive"))
    )
    (net (code "80") (name "Net-(IC12-TRIM)") (class "Default")
      (node (ref "IC12") (pin "P$5") (pinfunction "TRIM_P$5") (pintype "bidirectional"))
      (node (ref "R49") (pin "1") (pinfunction "1_1") (pintype "passive"))
    )
    (net (code "81") (name "Net-(IC13-OUTL)") (class "Default")
      (node (ref "IC13") (pin "6") (pinfunction "OUTL_6") (pintype "bidirectional"))
      (node (ref "R35") (pin "2") (pinfunction "2_2") (pintype "passive"))
    )
    (net (code "82") (name "Net-(IC13-OUTR)") (class "Default")
      (node (ref "IC13") (pin "7") (pinfunction "OUTR_7") (pintype "bidirectional"))
      (node (ref "R36") (pin "2") (pinfunction "2_2") (pintype "passive"))
    )
    (net (code "83") (name "Net-(LED1-PadA)") (class "Default")
      (node (ref "LED1") (pin "A") (pinfunction "A_A") (pintype "passive"))
      (node (ref "R43") (pin "1") (pinfunction "1_1") (pintype "passive"))
    )
    (net (code "84") (name "Net-(LED2-PadA)") (class "Default")
      (node (ref "LED2") (pin "A") (pinfunction "A_A") (pintype "passive"))
      (node (ref "R44") (pin "1") (pinfunction "1_1") (pintype "passive"))
    )
    (net (code "85") (name "Net-(LED3-PadA)") (class "Default")
      (node (ref "LED3") (pin "A") (pinfunction "A_A") (pintype "passive"))
      (node (ref "R45") (pin "1") (pinfunction "1_1") (pintype "passive"))
    )
    (net (code "86") (name "Net-(LED4-PadA)") (class "Default")
      (node (ref "LED4") (pin "A") (pinfunction "A_A") (pintype "passive"))
      (node (ref "R46") (pin "1") (pinfunction "1_1") (pintype "passive"))
    )
    (net (code "87") (name "Net-(LED5-PadA)") (class "Default")
      (node (ref "LED5") (pin "A") (pinfunction "A_A") (pintype "passive"))
      (node (ref "R47") (pin "1") (pinfunction "1_1") (pintype "passive"))
    )
    (net (code "88") (name "Net-(OSC1-OUT)") (class "Default")
      (node (ref "OSC1") (pin "3") (pinfunction "OUT_3") (pintype "output"))
      (node (ref "R48") (pin "1") (pinfunction "1_1") (pintype "passive"))
    )
    (net (code "89") (name "Net-(TP10-P$1)") (class "Default")
      (node (ref "BAL_LEFT") (pin "T") (pinfunction "T_T") (pintype "passive"))
      (node (ref "R14") (pin "2") (pinfunction "2_2") (pintype "passive"))
      (node (ref "TP10") (pin "1") (pinfunction "P$1_1") (pintype "bidirectional"))
    )
    (net (code "90") (name "Net-(TP11-P$1)") (class "Default")
      (node (ref "BAL_LEFT") (pin "R") (pinfunction "R_R") (pintype "passive"))
      (node (ref "R15") (pin "2") (pinfunction "2_2") (pintype "passive"))
      (node (ref "TP11") (pin "1") (pinfunction "P$1_1") (pintype "bidirectional"))
    )
    (net (code "91") (name "Net-(TP12-P$1)") (class "Default")
      (node (ref "J1") (pin "L_SIG") (pinfunction "L_SIG_L_SIG") (pintype "passive"))
      (node (ref "R13") (pin "2") (pinfunction "2_2") (pintype "passive"))
      (node (ref "TP12") (pin "1") (pinfunction "P$1_1") (pintype "bidirectional"))
    )
    (net (code "92") (name "Net-(TP15-P$1)") (class "Default")
      (node (ref "BAL_RIGHT") (pin "T") (pinfunction "T_T") (pintype "passive"))
      (node (ref "R30") (pin "2") (pinfunction "2_2") (pintype "passive"))
      (node (ref "TP15") (pin "1") (pinfunction "P$1_1") (pintype "bidirectional"))
    )
    (net (code "93") (name "Net-(TP16-P$1)") (class "Default")
      (node (ref "BAL_RIGHT") (pin "R") (pinfunction "R_R") (pintype "passive"))
      (node (ref "R31") (pin "2") (pinfunction "2_2") (pintype "passive"))
      (node (ref "TP16") (pin "1") (pinfunction "P$1_1") (pintype "bidirectional"))
    )
    (net (code "94") (name "Net-(TP17-P$1)") (class "Default")
      (node (ref "J1") (pin "R_SIG") (pinfunction "R_SIG_R_SIG") (pintype "passive"))
      (node (ref "R29") (pin "2") (pinfunction "2_2") (pintype "passive"))
      (node (ref "TP17") (pin "1") (pinfunction "P$1_1") (pintype "bidirectional"))
    )
    (net (code "95") (name "Net-(X1B-1)") (class "Default")
      (node (ref "X1") (pin "P$2") (pinfunction "1_P$2") (pintype "passive"))
      (node (ref "X2") (pin "P$2") (pinfunction "1_P$2") (pintype "passive"))
    )
    (net (code "96") (name "Net-(X1C-1)") (class "Default")
      (node (ref "X1") (pin "P$3") (pinfunction "1_P$3") (pintype "passive"))
      (node (ref "X2") (pin "P$3") (pinfunction "1_P$3") (pintype "passive"))
    )
    (net (code "97") (name "unconnected-(BAL_LEFT-PadRN)") (class "Default")
      (node (ref "BAL_LEFT") (pin "RN") (pinfunction "RN_RN") (pintype "passive"))
    )
    (net (code "98") (name "unconnected-(BAL_LEFT-PadSN)") (class "Default")
      (node (ref "BAL_LEFT") (pin "SN") (pinfunction "SN_SN") (pintype "passive"))
    )
    (net (code "99") (name "unconnected-(BAL_LEFT-PadTN)") (class "Default")
      (node (ref "BAL_LEFT") (pin "TN") (pinfunction "TN_TN") (pintype "passive"))
    )
    (net (code "100") (name "unconnected-(BAL_RIGHT-PadRN)") (class "Default")
      (node (ref "BAL_RIGHT") (pin "RN") (pinfunction "RN_RN") (pintype "passive"))
    )
    (net (code "101") (name "unconnected-(BAL_RIGHT-PadSN)") (class "Default")
      (node (ref "BAL_RIGHT") (pin "SN") (pinfunction "SN_SN") (pintype "passive"))
    )
    (net (code "102") (name "unconnected-(BAL_RIGHT-PadTN)") (class "Default")
      (node (ref "BAL_RIGHT") (pin "TN") (pinfunction "TN_TN") (pintype "passive"))
    )
    (net (code "103") (name "unconnected-(IC1-ZERO_LEFT-Pad1)") (class "Default")
      (node (ref "IC1") (pin "1") (pinfunction "ZERO_LEFT_1") (pintype "bidirectional"))
    )
    (net (code "104") (name "unconnected-(IC1-ZERO_RIGHT-Pad2)") (class "Default")
      (node (ref "IC1") (pin "2") (pinfunction "ZERO_RIGHT_2") (pintype "bidirectional"))
    )
    (net (code "105") (name "unconnected-(IC8-ERR-Pad6)") (class "Default")
      (node (ref "IC8") (pin "6") (pinfunction "ERR_6") (pintype "bidirectional"))
    )
    (net (code "106") (name "unconnected-(IC12-REM-PadP$1)") (class "Default")
      (node (ref "IC12") (pin "P$1") (pinfunction "REM_P$1") (pintype "bidirectional"))
    )
    (net (code "107") (name "unconnected-(IC14-ERR-Pad6)") (class "Default")
      (node (ref "IC14") (pin "6") (pinfunction "ERR_6") (pintype "bidirectional"))
    )
    (net (code "108") (name "unconnected-(J5-PadC)") (class "Default")
      (node (ref "J5") (pin "C") (pinfunction "C_C") (pintype "passive"))
    )
    (net (code "109") (name "unconnected-(OSC1-INH-Pad1)") (class "Default")
      (node (ref "OSC1") (pin "1") (pinfunction "INH_1") (pintype "bidirectional"))
    )
  )
)
